# octanis_v0_5.net
KiCad netlist of a schematic drawn in EAGLE
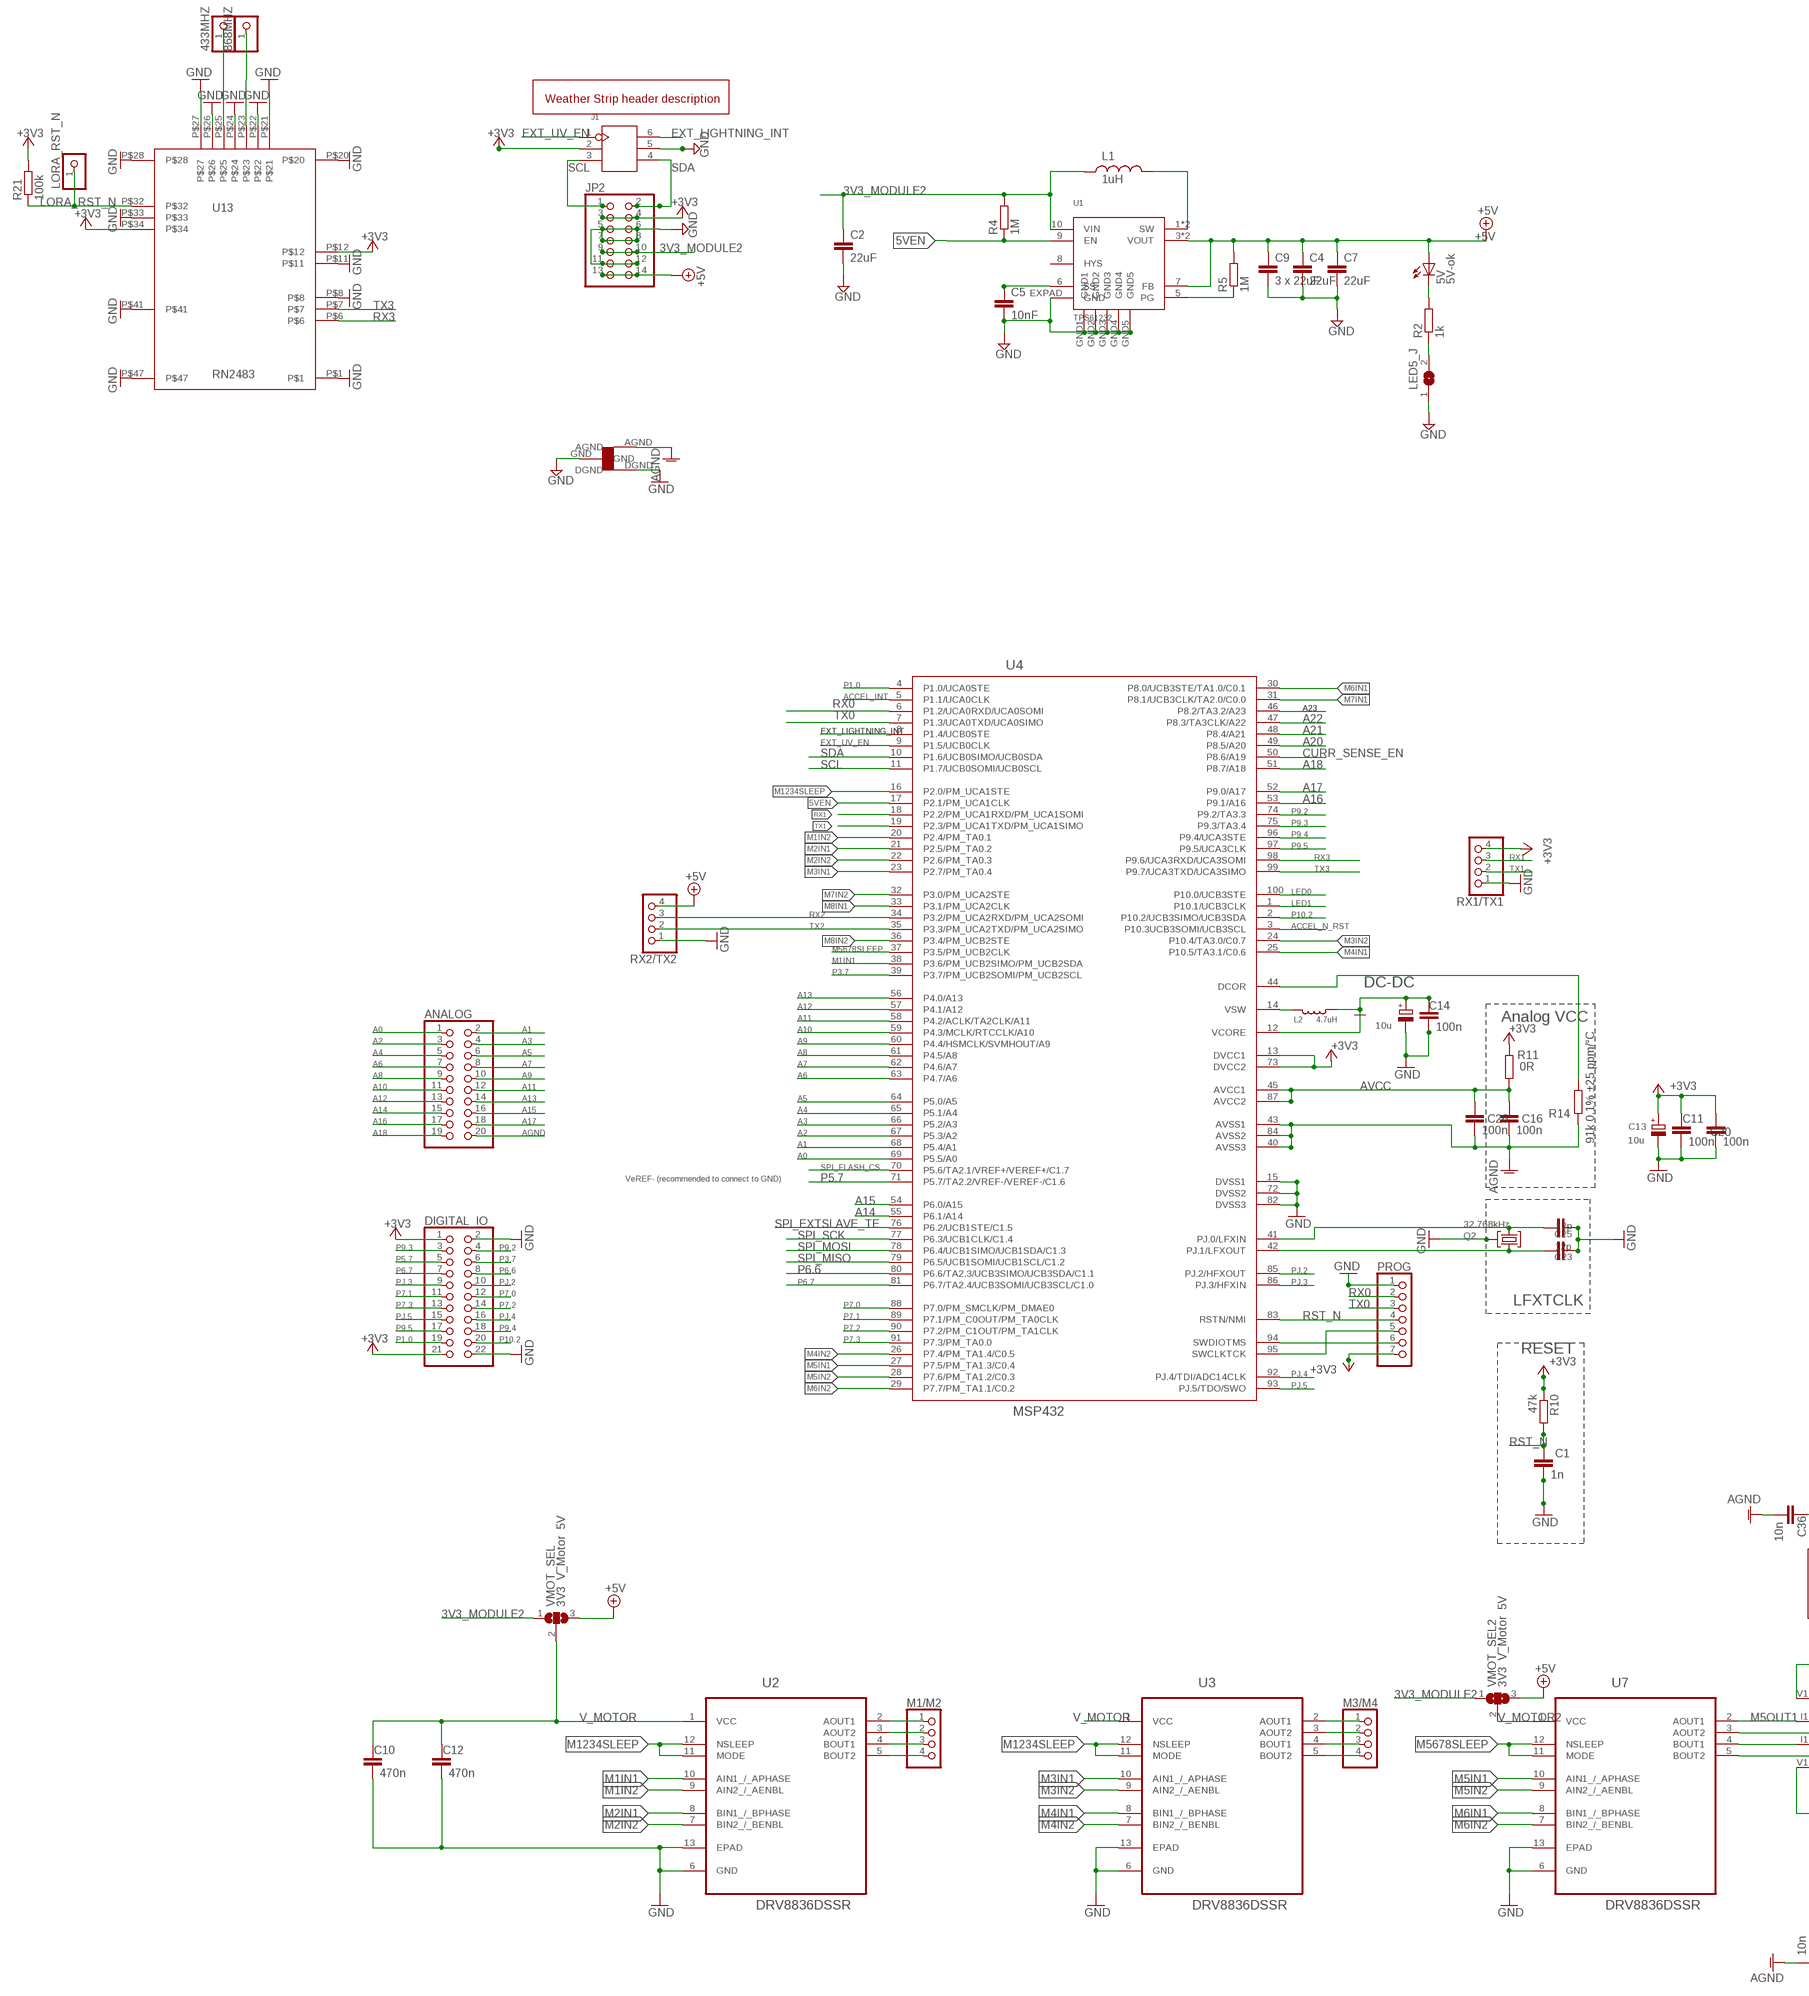
[diagram p0: schematic, sheet 1, part 1 of 2]
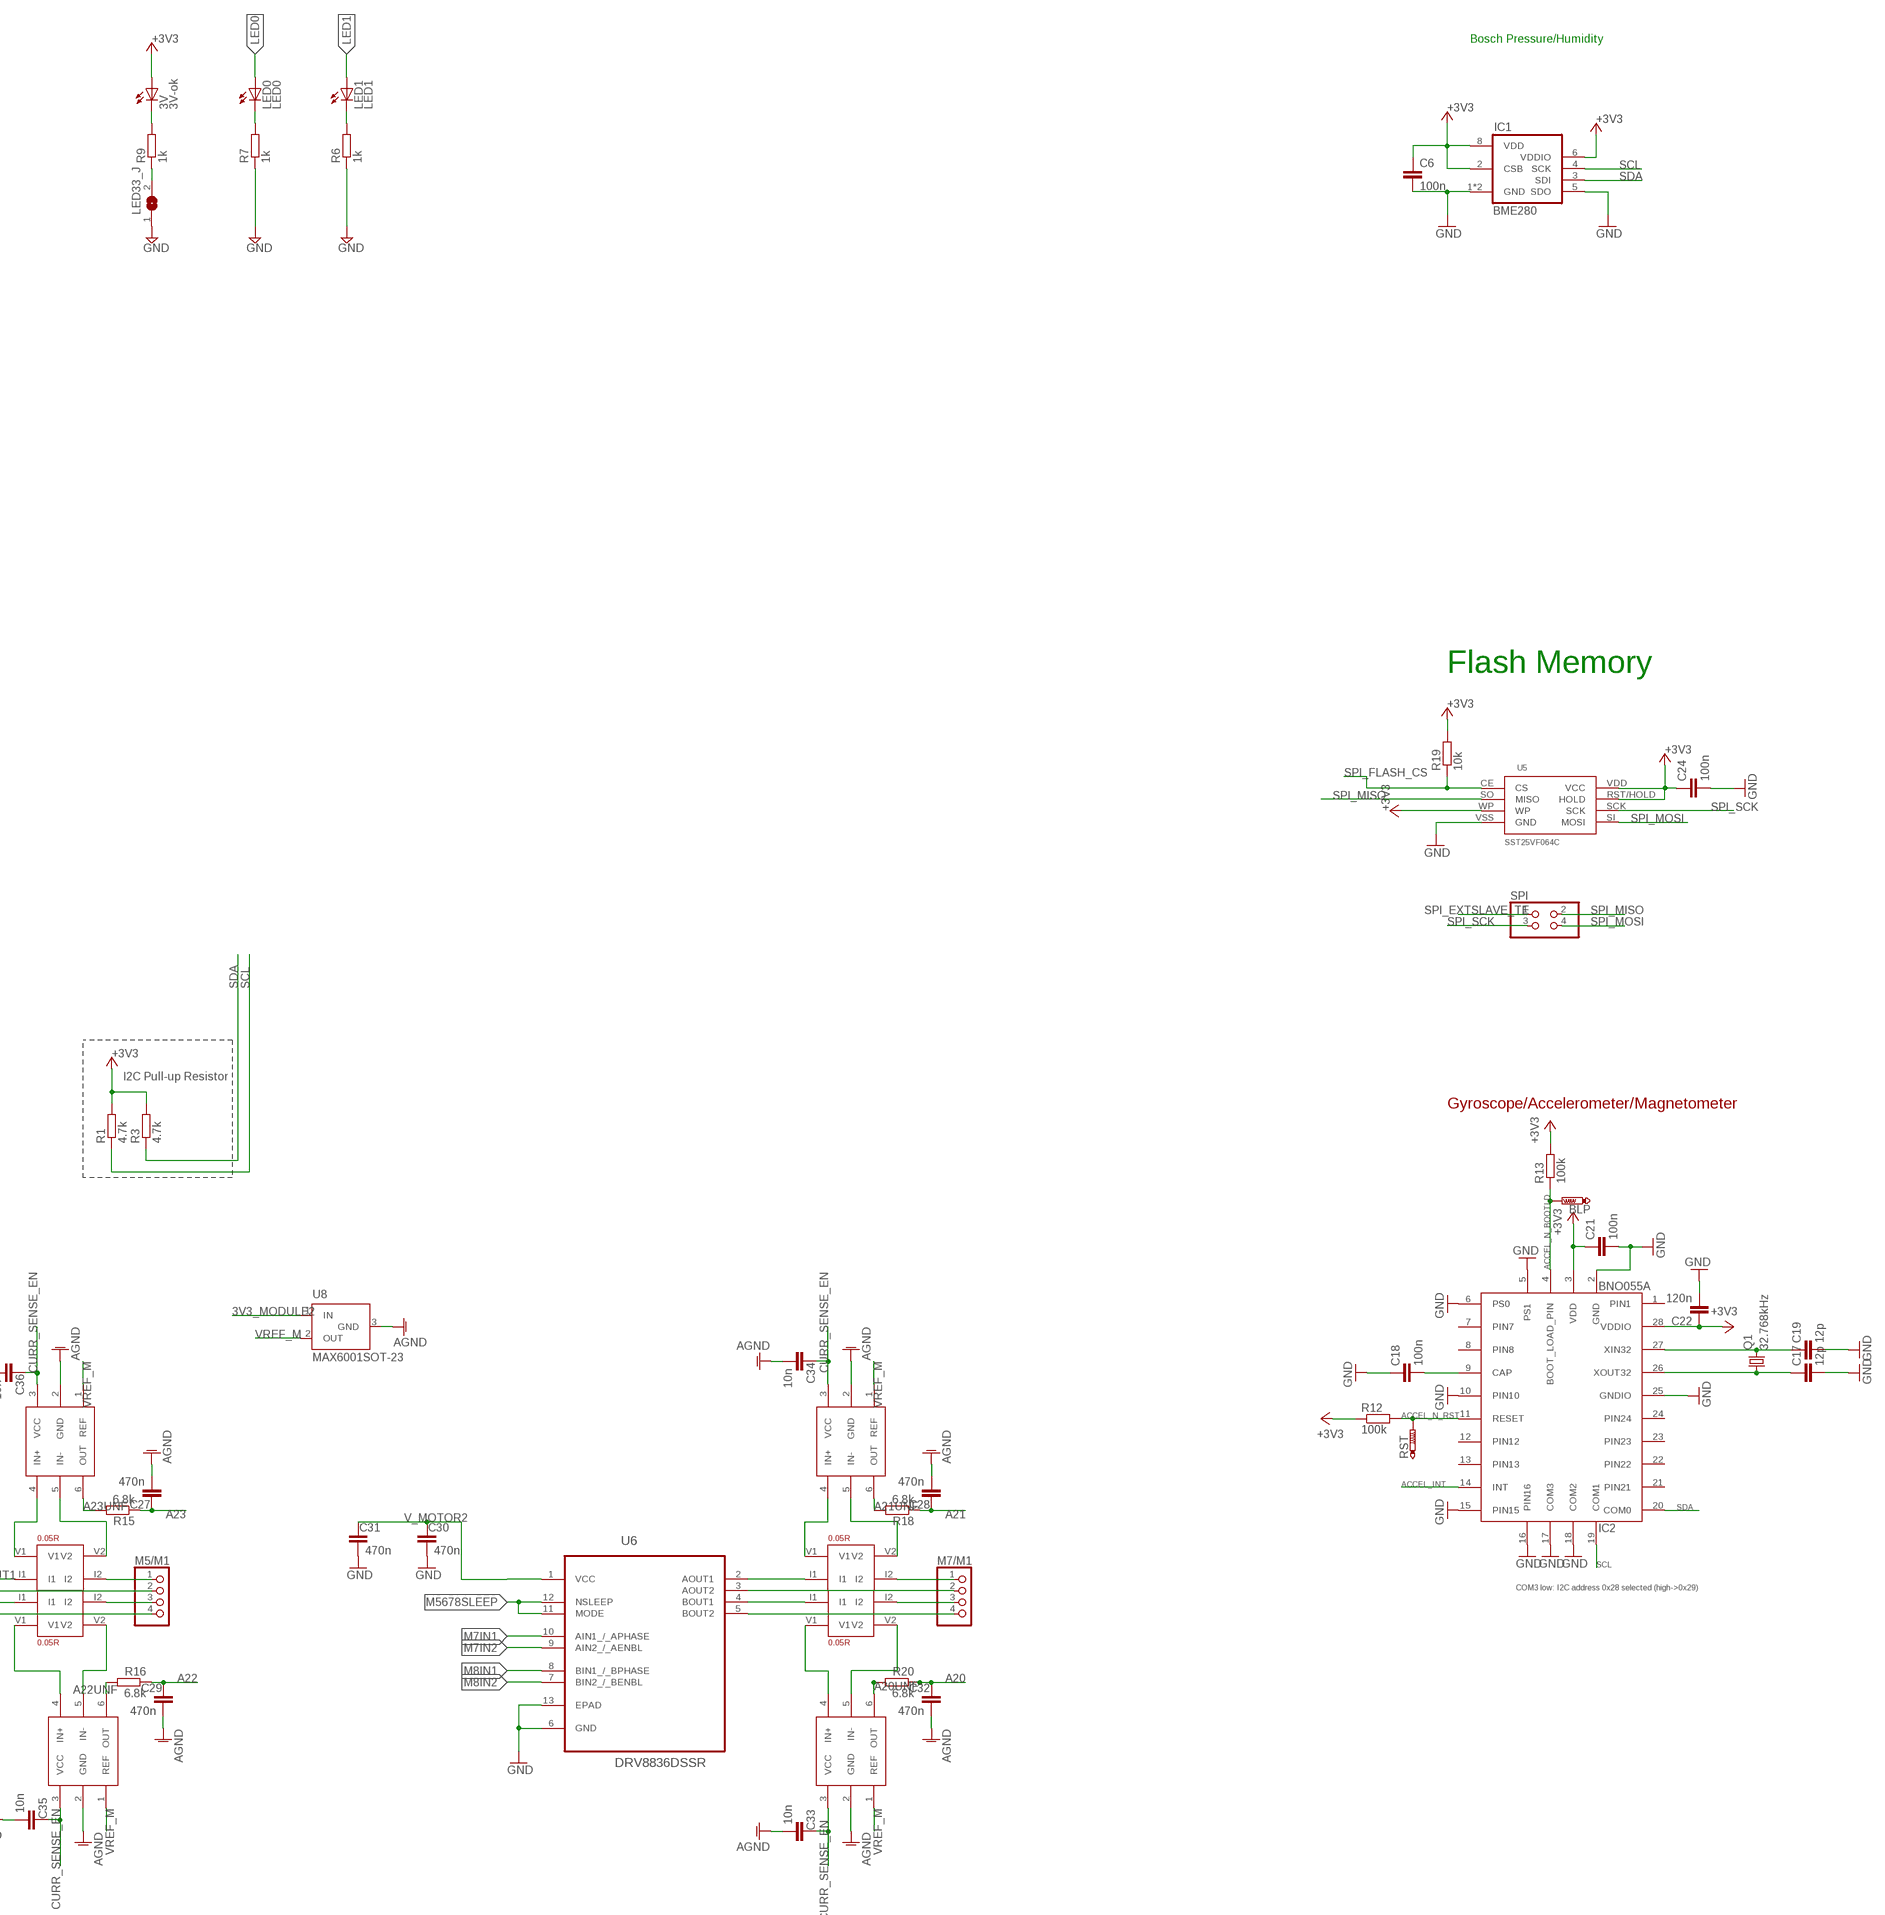
[diagram p1: schematic, sheet 1, part 2 of 2]

(export (version "E")
  (design (tool "Eeschema 10.0.6"))
  (components
    (comp (ref "3V")
      (value "3V-ok")
      (footprint "eagle-import:CHIPLED_0603")
      (libsource (lib "eagle-import") (part "LEDCHIPLED_0603"))
    )
    (comp (ref "5V")
      (value "5V-ok")
      (footprint "eagle-import:CHIPLED_0603")
      (libsource (lib "eagle-import") (part "LEDCHIPLED_0603"))
    )
    (comp (ref "433MHZ")
      (value "PINHD-1X1")
      (footprint "eagle-import:1X01")
      (libsource (lib "eagle-import") (part "PINHD-1X1"))
    )
    (comp (ref "868MHZ")
      (value "PINHD-1X1")
      (footprint "eagle-import:1X01")
      (libsource (lib "eagle-import") (part "PINHD-1X1"))
    )
    (comp (ref "ANALOG")
      (value "PINHD-2X10")
      (footprint "eagle-import:2X10")
      (libsource (lib "eagle-import") (part "PINHD-2X10"))
    )
    (comp (ref "BLP")
      (value "PTR1B1,27")
      (footprint "eagle-import:B1,27")
      (libsource (lib "eagle-import") (part "PTR1B1,27"))
    )
    (comp (ref "C1")
      (value "1n")
      (footprint "eagle-import:C0603")
      (libsource (lib "eagle-import") (part "C-EUC0603"))
    )
    (comp (ref "C2")
      (value "22uF")
      (footprint "eagle-import:C0603")
      (libsource (lib "eagle-import") (part "C-EUC0603"))
    )
    (comp (ref "C4")
      (value "22uF")
      (footprint "eagle-import:C0603")
      (libsource (lib "eagle-import") (part "C-EUC0603"))
    )
    (comp (ref "C5")
      (value "10nF")
      (footprint "eagle-import:C0603")
      (libsource (lib "eagle-import") (part "C-EUC0603"))
    )
    (comp (ref "C6")
      (value "100n")
      (footprint "eagle-import:C0603")
      (libsource (lib "eagle-import") (part "C-EUC0603"))
    )
    (comp (ref "C7")
      (value "22uF")
      (footprint "eagle-import:C0603")
      (libsource (lib "eagle-import") (part "C-EUC0603"))
    )
    (comp (ref "C9")
      (value "3 x 22uF")
      (footprint "eagle-import:C0603")
      (libsource (lib "eagle-import") (part "C-EUC0603"))
    )
    (comp (ref "C10")
      (value "470n")
      (footprint "eagle-import:C0603")
      (libsource (lib "eagle-import") (part "C-EUC0603"))
    )
    (comp (ref "C11")
      (value "100n")
      (footprint "eagle-import:C0603")
      (libsource (lib "eagle-import") (part "C-EUC0603"))
    )
    (comp (ref "C12")
      (value "470n")
      (footprint "eagle-import:C0603")
      (libsource (lib "eagle-import") (part "C-EUC0603"))
    )
    (comp (ref "C13")
      (value "10u")
      (footprint "eagle-import:A_3216-18R")
      (libsource (lib "eagle-import") (part "CPOL-EUA/3216-18R"))
    )
    (comp (ref "C14")
      (value "100n")
      (footprint "eagle-import:C0603")
      (libsource (lib "eagle-import") (part "C-EUC0603"))
    )
    (comp (ref "C15")
      (value "10u")
      (footprint "eagle-import:A_3216-18R")
      (libsource (lib "eagle-import") (part "CPOL-EUA/3216-18R"))
    )
    (comp (ref "C16")
      (value "100n")
      (footprint "eagle-import:C0402")
      (libsource (lib "eagle-import") (part "C-EUC0402"))
    )
    (comp (ref "C17")
      (value "12p")
      (footprint "eagle-import:C0603")
      (libsource (lib "eagle-import") (part "C-EUC0603"))
    )
    (comp (ref "C18")
      (value "100n")
      (footprint "eagle-import:C0603")
      (libsource (lib "eagle-import") (part "C-EUC0603"))
    )
    (comp (ref "C19")
      (value "12p")
      (footprint "eagle-import:C0603")
      (libsource (lib "eagle-import") (part "C-EUC0603"))
    )
    (comp (ref "C20")
      (value "100n")
      (footprint "eagle-import:C0603")
      (libsource (lib "eagle-import") (part "C-EUC0603"))
    )
    (comp (ref "C21")
      (value "100n")
      (footprint "eagle-import:C0603")
      (libsource (lib "eagle-import") (part "C-EUC0603"))
    )
    (comp (ref "C22")
      (value "120n")
      (footprint "eagle-import:C0603")
      (libsource (lib "eagle-import") (part "C-EUC0603"))
    )
    (comp (ref "C23")
      (value "12p")
      (footprint "eagle-import:C0402")
      (libsource (lib "eagle-import") (part "C-EUC0402"))
    )
    (comp (ref "C24")
      (value "100n")
      (footprint "eagle-import:C0603")
      (libsource (lib "eagle-import") (part "C-EUC0603"))
    )
    (comp (ref "C25")
      (value "12p")
      (footprint "eagle-import:C0402")
      (libsource (lib "eagle-import") (part "C-EUC0402"))
    )
    (comp (ref "C26")
      (value "100n")
      (footprint "eagle-import:C0402")
      (libsource (lib "eagle-import") (part "C-EUC0402"))
    )
    (comp (ref "C27")
      (value "470n")
      (footprint "eagle-import:C0603")
      (libsource (lib "eagle-import") (part "C-EUC0603"))
    )
    (comp (ref "C28")
      (value "470n")
      (footprint "eagle-import:C0603")
      (libsource (lib "eagle-import") (part "C-EUC0603"))
    )
    (comp (ref "C29")
      (value "470n")
      (footprint "eagle-import:C0603")
      (libsource (lib "eagle-import") (part "C-EUC0603"))
    )
    (comp (ref "C30")
      (value "470n")
      (footprint "eagle-import:C0603")
      (libsource (lib "eagle-import") (part "C-EUC0603"))
    )
    (comp (ref "C31")
      (value "470n")
      (footprint "eagle-import:C0603")
      (libsource (lib "eagle-import") (part "C-EUC0603"))
    )
    (comp (ref "C32")
      (value "470n")
      (footprint "eagle-import:C0603")
      (libsource (lib "eagle-import") (part "C-EUC0603"))
    )
    (comp (ref "C33")
      (value "10n")
      (footprint "eagle-import:C0603")
      (libsource (lib "eagle-import") (part "C-EUC0603"))
    )
    (comp (ref "C34")
      (value "10n")
      (footprint "eagle-import:C0603")
      (libsource (lib "eagle-import") (part "C-EUC0603"))
    )
    (comp (ref "C35")
      (value "10n")
      (footprint "eagle-import:C0603")
      (libsource (lib "eagle-import") (part "C-EUC0603"))
    )
    (comp (ref "C36")
      (value "10n")
      (footprint "eagle-import:C0603")
      (libsource (lib "eagle-import") (part "C-EUC0603"))
    )
    (comp (ref "DIGITAL_IO")
      (value "PINHD-2X11")
      (footprint "eagle-import:2X11")
      (libsource (lib "eagle-import") (part "PINHD-2X11"))
    )
    (comp (ref "IC1")
      (value "BME280")
      (footprint "eagle-import:BME280")
      (libsource (lib "eagle-import") (part "BME280"))
    )
    (comp (ref "IC2")
      (value "BNO055A")
      (footprint "eagle-import:BNO055")
      (libsource (lib "eagle-import") (part "BNO055A"))
    )
    (comp (ref "J1")
      (value "SMD-BLUE-FEMALE-HEADER-VERT(2X3P-2.54)")
      (footprint "eagle-import:H2X3-SMD-2.54")
      (fields (field (name "MPN") "F185-1203A1BMYA1"))
      (libsource (lib "eagle-import") (part "SMD-BLUE-FEMALE-HEADER-VERT(2X3P-2.54)"))
    )
    (comp (ref "JP2")
      (value "PINHD-2X7")
      (footprint "eagle-import:2X07")
      (libsource (lib "eagle-import") (part "PINHD-2X7"))
    )
    (comp (ref "L1")
      (value "1uH")
      (footprint "eagle-import:XFL4020")
      (libsource (lib "eagle-import") (part "XFL4020"))
    )
    (comp (ref "L2")
      (value "4.7uH")
      (footprint "eagle-import:0806")
      (libsource (lib "eagle-import") (part "LQM2MP_G0"))
    )
    (comp (ref "LED0")
      (value "LED0")
      (footprint "eagle-import:CHIPLED_0603")
      (libsource (lib "eagle-import") (part "LEDCHIPLED_0603"))
    )
    (comp (ref "LED1")
      (value "LED1")
      (footprint "eagle-import:CHIPLED_0603")
      (libsource (lib "eagle-import") (part "LEDCHIPLED_0603"))
    )
    (comp (ref "LED5_J")
      (value "SJ")
      (footprint "eagle-import:SJ")
      (libsource (lib "eagle-import") (part "SJ"))
    )
    (comp (ref "LED33_J")
      (value "SJ")
      (footprint "eagle-import:SJ")
      (libsource (lib "eagle-import") (part "SJ"))
    )
    (comp (ref "LORA_RST_N")
      (value "PINHD-1X1")
      (footprint "eagle-import:1X01")
      (libsource (lib "eagle-import") (part "PINHD-1X1"))
    )
    (comp (ref "M1/M2")
      (value "PINHD-1X04_2.54-S")
      (footprint "eagle-import:1X04-S")
      (libsource (lib "eagle-import") (part "PINHD-1X04_2.54-S"))
    )
    (comp (ref "M3/M4")
      (value "PINHD-1X04_2.54-S")
      (footprint "eagle-import:1X04-S")
      (libsource (lib "eagle-import") (part "PINHD-1X04_2.54-S"))
    )
    (comp (ref "M5/M1")
      (value "PINHD-1X04_2.54-S")
      (footprint "eagle-import:1X04-S")
      (libsource (lib "eagle-import") (part "PINHD-1X04_2.54-S"))
    )
    (comp (ref "M7/M1")
      (value "PINHD-1X04_2.54-S")
      (footprint "eagle-import:1X04-S")
      (libsource (lib "eagle-import") (part "PINHD-1X04_2.54-S"))
    )
    (comp (ref "PROG")
      (value "PINHD-1X72MM_SMD")
      (footprint "eagle-import:1X7SMD")
      (libsource (lib "eagle-import") (part "PINHD-1X72MM_SMD"))
    )
    (comp (ref "Q1")
      (value "32.768kHz")
      (footprint "eagle-import:FC-12M")
      (libsource (lib "eagle-import") (part "FC-12M"))
    )
    (comp (ref "Q2")
      (value "32.768kHz")
      (footprint "eagle-import:MS3V-T1R")
      (libsource (lib "eagle-import") (part "MS3V-T1R"))
    )
    (comp (ref "R1")
      (value "4.7k")
      (footprint "eagle-import:R0603")
      (libsource (lib "eagle-import") (part "R-EU_R0603"))
    )
    (comp (ref "R2")
      (value "1k")
      (footprint "eagle-import:R0603")
      (libsource (lib "eagle-import") (part "R-EU_R0603"))
    )
    (comp (ref "R3")
      (value "4.7k")
      (footprint "eagle-import:R0603")
      (libsource (lib "eagle-import") (part "R-EU_R0603"))
    )
    (comp (ref "R4")
      (value "1M")
      (footprint "eagle-import:R0603")
      (libsource (lib "eagle-import") (part "R-EU_R0603"))
    )
    (comp (ref "R5")
      (value "1M")
      (footprint "eagle-import:R0603")
      (libsource (lib "eagle-import") (part "R-EU_R0603"))
    )
    (comp (ref "R6")
      (value "1k")
      (footprint "eagle-import:R0603")
      (libsource (lib "eagle-import") (part "R-EU_R0603"))
    )
    (comp (ref "R7")
      (value "1k")
      (footprint "eagle-import:R0603")
      (libsource (lib "eagle-import") (part "R-EU_R0603"))
    )
    (comp (ref "R9")
      (value "1k")
      (footprint "eagle-import:R0603")
      (libsource (lib "eagle-import") (part "R-EU_R0603"))
    )
    (comp (ref "R10")
      (value "47k")
      (footprint "eagle-import:R0603")
      (libsource (lib "eagle-import") (part "R-EU_R0603"))
    )
    (comp (ref "R11")
      (value "0R")
      (footprint "eagle-import:R0402")
      (libsource (lib "eagle-import") (part "R-EU_R0402"))
    )
    (comp (ref "R12")
      (value "100k")
      (footprint "eagle-import:R0603")
      (libsource (lib "eagle-import") (part "R-EU_R0603"))
    )
    (comp (ref "R13")
      (value "100k")
      (footprint "eagle-import:R0603")
      (libsource (lib "eagle-import") (part "R-EU_R0603"))
    )
    (comp (ref "R14")
      (value "91k 0.1% ±25 ppm/°C")
      (footprint "eagle-import:R0402")
      (libsource (lib "eagle-import") (part "R-EU_R0402"))
    )
    (comp (ref "R15")
      (value "6.8k")
      (footprint "eagle-import:R0603")
      (libsource (lib "eagle-import") (part "R-EU_R0603"))
    )
    (comp (ref "R16")
      (value "6.8k")
      (footprint "eagle-import:R0603")
      (libsource (lib "eagle-import") (part "R-EU_R0603"))
    )
    (comp (ref "R18")
      (value "6.8k")
      (footprint "eagle-import:R0603")
      (libsource (lib "eagle-import") (part "R-EU_R0603"))
    )
    (comp (ref "R19")
      (value "10k")
      (footprint "eagle-import:R0603")
      (libsource (lib "eagle-import") (part "R-EU_R0603"))
    )
    (comp (ref "R20")
      (value "6.8k")
      (footprint "eagle-import:R0603")
      (libsource (lib "eagle-import") (part "R-EU_R0603"))
    )
    (comp (ref "R21")
      (value "100k")
      (footprint "eagle-import:R0603")
      (libsource (lib "eagle-import") (part "R-EU_R0603"))
    )
    (comp (ref "RS1")
      (value "0.05R")
      (footprint "eagle-import:4PADS_RESISTOR")
      (libsource (lib "eagle-import") (part "CURRENT_RESISTOR"))
    )
    (comp (ref "RS2")
      (value "0.05R")
      (footprint "eagle-import:4PADS_RESISTOR")
      (libsource (lib "eagle-import") (part "CURRENT_RESISTOR"))
    )
    (comp (ref "RS3")
      (value "0.05R")
      (footprint "eagle-import:4PADS_RESISTOR")
      (libsource (lib "eagle-import") (part "CURRENT_RESISTOR"))
    )
    (comp (ref "RS4")
      (value "0.05R")
      (footprint "eagle-import:4PADS_RESISTOR")
      (libsource (lib "eagle-import") (part "CURRENT_RESISTOR"))
    )
    (comp (ref "RST")
      (value "PTR1B1,27")
      (footprint "eagle-import:B1,27")
      (libsource (lib "eagle-import") (part "PTR1B1,27"))
    )
    (comp (ref "RX1/TX1")
      (value "PINHD-1X04_2.54-S")
      (footprint "eagle-import:1X04-S")
      (libsource (lib "eagle-import") (part "PINHD-1X04_2.54-S"))
    )
    (comp (ref "RX2/TX2")
      (value "PINHD-1X04_2.54-S")
      (footprint "eagle-import:1X04-S")
      (libsource (lib "eagle-import") (part "PINHD-1X04_2.54-S"))
    )
    (comp (ref "SPI")
      (value "PINHD-2X2")
      (footprint "eagle-import:2X02")
      (libsource (lib "eagle-import") (part "PINHD-2X2"))
    )
    (comp (ref "U$1")
      (value "WEATHER_STRIP_DOCU")
      (footprint "eagle-import:WEATHER_STRIP_DOCU")
      (libsource (lib "eagle-import") (part "WEATHER_STRIP_DOCU"))
    )
    (comp (ref "U$100")
      (value "STARGND")
      (footprint "eagle-import:STAR")
      (libsource (lib "eagle-import") (part "STARGND"))
    )
    (comp (ref "U1")
      (value "TPS61232")
      (footprint "eagle-import:S-PVSON-N10")
      (libsource (lib "eagle-import") (part "TPS61232"))
    )
    (comp (ref "U2")
      (value "DRV8836DSSR")
      (footprint "eagle-import:SON50P200X300X80-13N")
      (fields (field (name "MPN") "DRV8836DSSR "))
      (libsource (lib "eagle-import") (part "DRV8836DSSR"))
    )
    (comp (ref "U3")
      (value "DRV8836DSSR")
      (footprint "eagle-import:SON50P200X300X80-13N")
      (fields (field (name "MPN") "DRV8836DSSR "))
      (libsource (lib "eagle-import") (part "DRV8836DSSR"))
    )
    (comp (ref "U4")
      (value "MSP432")
      (footprint "eagle-import:PZ100")
      (libsource (lib "eagle-import") (part "MSP432"))
    )
    (comp (ref "U5")
      (value "SST25VF064C")
      (footprint "eagle-import:SOIC_8-LEAD")
      (libsource (lib "eagle-import") (part "SST25VF064C"))
    )
    (comp (ref "U6")
      (value "DRV8836DSSR")
      (footprint "eagle-import:SON50P200X300X80-13N")
      (fields (field (name "MPN") "DRV8836DSSR "))
      (libsource (lib "eagle-import") (part "DRV8836DSSR"))
    )
    (comp (ref "U7")
      (value "DRV8836DSSR")
      (footprint "eagle-import:SON50P200X300X80-13N")
      (fields (field (name "MPN") "DRV8836DSSR "))
      (libsource (lib "eagle-import") (part "DRV8836DSSR"))
    )
    (comp (ref "U8")
      (value "MAX6001SOT-23")
      (footprint "eagle-import:MAX6001")
      (libsource (lib "eagle-import") (part "MAX6001SOT-23"))
    )
    (comp (ref "U9")
      (value "INA210")
      (footprint "eagle-import:SC70-6")
      (libsource (lib "eagle-import") (part "INA213"))
    )
    (comp (ref "U10")
      (value "INA210")
      (footprint "eagle-import:SC70-6")
      (libsource (lib "eagle-import") (part "INA213"))
    )
    (comp (ref "U11")
      (value "INA210")
      (footprint "eagle-import:SC70-6")
      (libsource (lib "eagle-import") (part "INA213"))
    )
    (comp (ref "U12")
      (value "INA210")
      (footprint "eagle-import:SC70-6")
      (libsource (lib "eagle-import") (part "INA213"))
    )
    (comp (ref "U13")
      (value "RN2483")
      (footprint "eagle-import:RN2483")
      (libsource (lib "eagle-import") (part "RN2483"))
    )
    (comp (ref "VMOT_SEL")
      (value "3V3 V_Motor 5V")
      (footprint "eagle-import:SJ_2")
      (libsource (lib "eagle-import") (part "SJ2W"))
    )
    (comp (ref "VMOT_SEL2")
      (value "3V3 V_Motor 5V")
      (footprint "eagle-import:SJ_2")
      (libsource (lib "eagle-import") (part "SJ2W"))
    )
  )
  (nets
    (net (code "1") (name "+3V3") (class "Default")
      (node (ref "3V") (pin "A") (pinfunction "A_A") (pintype "passive"))
      (node (ref "C11") (pin "2") (pinfunction "2_2") (pintype "passive"))
      (node (ref "C13") (pin "+") (pinfunction "+_+") (pintype "passive"))
      (node (ref "C20") (pin "2") (pinfunction "2_2") (pintype "passive"))
      (node (ref "C21") (pin "1") (pinfunction "1_1") (pintype "passive"))
      (node (ref "C22") (pin "1") (pinfunction "1_1") (pintype "passive"))
      (node (ref "C24") (pin "1") (pinfunction "1_1") (pintype "passive"))
      (node (ref "C6") (pin "1") (pinfunction "1_1") (pintype "passive"))
      (node (ref "DIGITAL_IO") (pin "1") (pinfunction "1_1") (pintype "passive"))
      (node (ref "DIGITAL_IO") (pin "21") (pinfunction "21_21") (pintype "passive"))
      (node (ref "IC1") (pin "2") (pinfunction "CSB_2") (pintype "input"))
      (node (ref "IC1") (pin "6") (pinfunction "VDDIO_6") (pintype "power_in"))
      (node (ref "IC1") (pin "8") (pinfunction "VDD_8") (pintype "power_in"))
      (node (ref "IC2") (pin "28") (pinfunction "VDDIO_28") (pintype "bidirectional"))
      (node (ref "IC2") (pin "3") (pinfunction "VDD_3") (pintype "bidirectional"))
      (node (ref "J1") (pin "2") (pinfunction "2_2") (pintype "bidirectional"))
      (node (ref "JP2") (pin "3") (pinfunction "3_3") (pintype "passive"))
      (node (ref "JP2") (pin "4") (pinfunction "4_4") (pintype "passive"))
      (node (ref "PROG") (pin "7") (pinfunction "7_7") (pintype "passive"))
      (node (ref "R1") (pin "2") (pinfunction "2_2") (pintype "passive"))
      (node (ref "R10") (pin "1") (pinfunction "1_1") (pintype "passive"))
      (node (ref "R11") (pin "2") (pinfunction "2_2") (pintype "passive"))
      (node (ref "R12") (pin "1") (pinfunction "1_1") (pintype "passive"))
      (node (ref "R13") (pin "2") (pinfunction "2_2") (pintype "passive"))
      (node (ref "R19") (pin "2") (pinfunction "2_2") (pintype "passive"))
      (node (ref "R21") (pin "2") (pinfunction "2_2") (pintype "passive"))
      (node (ref "R3") (pin "2") (pinfunction "2_2") (pintype "passive"))
      (node (ref "RX1/TX1") (pin "4") (pinfunction "4_4") (pintype "passive"))
      (node (ref "U13") (pin "P$12") (pinfunction "P$12_P$12") (pintype "bidirectional"))
      (node (ref "U13") (pin "P$34") (pinfunction "P$34_P$34") (pintype "bidirectional"))
      (node (ref "U4") (pin "13") (pinfunction "DVCC1_13") (pintype "power_in"))
      (node (ref "U4") (pin "73") (pinfunction "DVCC2_73") (pintype "power_in"))
      (node (ref "U5") (pin "RST/HOLD") (pinfunction "HOLD_RST/HOLD") (pintype "bidirectional"))
      (node (ref "U5") (pin "VDD") (pinfunction "VCC_VDD") (pintype "bidirectional"))
      (node (ref "U5") (pin "WP") (pinfunction "WP_WP") (pintype "bidirectional"))
    )
    (net (code "2") (name "+5V") (class "Default")
      (node (ref "5V") (pin "A") (pinfunction "A_A") (pintype "passive"))
      (node (ref "C4") (pin "1") (pinfunction "1_1") (pintype "passive"))
      (node (ref "C7") (pin "1") (pinfunction "1_1") (pintype "passive"))
      (node (ref "C9") (pin "1") (pinfunction "1_1") (pintype "passive"))
      (node (ref "JP2") (pin "13") (pinfunction "13_13") (pintype "passive"))
      (node (ref "JP2") (pin "14") (pinfunction "14_14") (pintype "passive"))
      (node (ref "R5") (pin "2") (pinfunction "2_2") (pintype "passive"))
      (node (ref "RX2/TX2") (pin "4") (pinfunction "4_4") (pintype "passive"))
      (node (ref "U1") (pin "3") (pinfunction "VOUT_3") (pintype "power_in"))
      (node (ref "U1") (pin "4") (pinfunction "VOUT_4") (pintype "power_in"))
      (node (ref "U1") (pin "7") (pinfunction "FB_7") (pintype "input"))
      (node (ref "VMOT_SEL") (pin "3") (pinfunction "3_3") (pintype "passive"))
      (node (ref "VMOT_SEL2") (pin "3") (pinfunction "3_3") (pintype "passive"))
    )
    (net (code "3") (name "/3V3_MODULE2") (class "Default")
      (node (ref "C2") (pin "1") (pinfunction "1_1") (pintype "passive"))
      (node (ref "JP2") (pin "10") (pinfunction "10_10") (pintype "passive"))
      (node (ref "JP2") (pin "9") (pinfunction "9_9") (pintype "passive"))
      (node (ref "L1") (pin "P$1") (pinfunction "1_P$1") (pintype "passive"))
      (node (ref "R4") (pin "2") (pinfunction "2_2") (pintype "passive"))
      (node (ref "U1") (pin "10") (pinfunction "VIN_10") (pintype "input"))
      (node (ref "U8") (pin "1") (pinfunction "IN_1") (pintype "input"))
      (node (ref "VMOT_SEL") (pin "1") (pinfunction "1_1") (pintype "passive"))
      (node (ref "VMOT_SEL2") (pin "1") (pinfunction "1_1") (pintype "passive"))
    )
    (net (code "4") (name "/A0") (class "Default")
      (node (ref "ANALOG") (pin "1") (pinfunction "1_1") (pintype "passive"))
      (node (ref "U4") (pin "69") (pinfunction "P5.5/A0_69") (pintype "power_in"))
    )
    (net (code "5") (name "/A1") (class "Default")
      (node (ref "ANALOG") (pin "2") (pinfunction "2_2") (pintype "passive"))
      (node (ref "U4") (pin "68") (pinfunction "P5.4/A1_68") (pintype "power_in"))
    )
    (net (code "6") (name "/A2") (class "Default")
      (node (ref "ANALOG") (pin "3") (pinfunction "3_3") (pintype "passive"))
      (node (ref "U4") (pin "67") (pinfunction "P5.3/A2_67") (pintype "power_in"))
    )
    (net (code "7") (name "/A3") (class "Default")
      (node (ref "ANALOG") (pin "4") (pinfunction "4_4") (pintype "passive"))
      (node (ref "U4") (pin "66") (pinfunction "P5.2/A3_66") (pintype "power_in"))
    )
    (net (code "8") (name "/A4") (class "Default")
      (node (ref "ANALOG") (pin "5") (pinfunction "5_5") (pintype "passive"))
      (node (ref "U4") (pin "65") (pinfunction "P5.1/A4_65") (pintype "power_in"))
    )
    (net (code "9") (name "/A5") (class "Default")
      (node (ref "ANALOG") (pin "6") (pinfunction "6_6") (pintype "passive"))
      (node (ref "U4") (pin "64") (pinfunction "P5.0/A5_64") (pintype "power_in"))
    )
    (net (code "10") (name "/A6") (class "Default")
      (node (ref "ANALOG") (pin "7") (pinfunction "7_7") (pintype "passive"))
      (node (ref "U4") (pin "63") (pinfunction "P4.7/A6_63") (pintype "power_in"))
    )
    (net (code "11") (name "/A7") (class "Default")
      (node (ref "ANALOG") (pin "8") (pinfunction "8_8") (pintype "passive"))
      (node (ref "U4") (pin "62") (pinfunction "P4.6/A7_62") (pintype "power_in"))
    )
    (net (code "12") (name "/A8") (class "Default")
      (node (ref "ANALOG") (pin "9") (pinfunction "9_9") (pintype "passive"))
      (node (ref "U4") (pin "61") (pinfunction "P4.5/A8_61") (pintype "power_in"))
    )
    (net (code "13") (name "/A9") (class "Default")
      (node (ref "ANALOG") (pin "10") (pinfunction "10_10") (pintype "passive"))
      (node (ref "U4") (pin "60") (pinfunction "P4.4/HSMCLK/SVMHOUT/A9_60") (pintype "power_in"))
    )
    (net (code "14") (name "/A10") (class "Default")
      (node (ref "ANALOG") (pin "11") (pinfunction "11_11") (pintype "passive"))
      (node (ref "U4") (pin "59") (pinfunction "P4.3/MCLK/RTCCLK/A10_59") (pintype "power_in"))
    )
    (net (code "15") (name "/A11") (class "Default")
      (node (ref "ANALOG") (pin "12") (pinfunction "12_12") (pintype "passive"))
      (node (ref "U4") (pin "58") (pinfunction "P4.2/ACLK/TA2CLK/A11_58") (pintype "power_in"))
    )
    (net (code "16") (name "/A12") (class "Default")
      (node (ref "ANALOG") (pin "13") (pinfunction "13_13") (pintype "passive"))
      (node (ref "U4") (pin "57") (pinfunction "P4.1/A12_57") (pintype "power_in"))
    )
    (net (code "17") (name "/A13") (class "Default")
      (node (ref "ANALOG") (pin "14") (pinfunction "14_14") (pintype "passive"))
      (node (ref "U4") (pin "56") (pinfunction "P4.0/A13_56") (pintype "power_in"))
    )
    (net (code "18") (name "/A14") (class "Default")
      (node (ref "ANALOG") (pin "15") (pinfunction "15_15") (pintype "passive"))
      (node (ref "U4") (pin "55") (pinfunction "P6.1/A14_55") (pintype "power_in"))
    )
    (net (code "19") (name "/A15") (class "Default")
      (node (ref "ANALOG") (pin "16") (pinfunction "16_16") (pintype "passive"))
      (node (ref "U4") (pin "54") (pinfunction "P6.0/A15_54") (pintype "power_in"))
    )
    (net (code "20") (name "/A16") (class "Default")
      (node (ref "ANALOG") (pin "17") (pinfunction "17_17") (pintype "passive"))
      (node (ref "U4") (pin "53") (pinfunction "P9.1/A16_53") (pintype "power_in"))
    )
    (net (code "21") (name "/A17") (class "Default")
      (node (ref "ANALOG") (pin "18") (pinfunction "18_18") (pintype "passive"))
      (node (ref "U4") (pin "52") (pinfunction "P9.0/A17_52") (pintype "power_in"))
    )
    (net (code "22") (name "/A18") (class "Default")
      (node (ref "ANALOG") (pin "19") (pinfunction "19_19") (pintype "passive"))
      (node (ref "U4") (pin "51") (pinfunction "P8.7/A18_51") (pintype "power_in"))
    )
    (net (code "23") (name "/A20") (class "Default")
      (node (ref "C32") (pin "2") (pinfunction "2_2") (pintype "passive"))
      (node (ref "R20") (pin "1") (pinfunction "1_1") (pintype "passive"))
      (node (ref "U4") (pin "49") (pinfunction "P8.5/A20_49") (pintype "power_in"))
    )
    (net (code "24") (name "/A20UNF") (class "Default")
      (node (ref "R20") (pin "2") (pinfunction "2_2") (pintype "passive"))
      (node (ref "U9") (pin "6") (pinfunction "OUT_6") (pintype "bidirectional"))
    )
    (net (code "25") (name "/A21") (class "Default")
      (node (ref "C28") (pin "2") (pinfunction "2_2") (pintype "passive"))
      (node (ref "R18") (pin "1") (pinfunction "1_1") (pintype "passive"))
      (node (ref "U4") (pin "48") (pinfunction "P8.4/A21_48") (pintype "power_in"))
    )
    (net (code "26") (name "/A21UNF") (class "Default")
      (node (ref "R18") (pin "2") (pinfunction "2_2") (pintype "passive"))
      (node (ref "U10") (pin "6") (pinfunction "OUT_6") (pintype "bidirectional"))
    )
    (net (code "27") (name "/A22") (class "Default")
      (node (ref "C29") (pin "2") (pinfunction "2_2") (pintype "passive"))
      (node (ref "R16") (pin "1") (pinfunction "1_1") (pintype "passive"))
      (node (ref "U4") (pin "47") (pinfunction "P8.3/TA3CLK/A22_47") (pintype "power_in"))
    )
    (net (code "28") (name "/A22UNF") (class "Default")
      (node (ref "R16") (pin "2") (pinfunction "2_2") (pintype "passive"))
      (node (ref "U11") (pin "6") (pinfunction "OUT_6") (pintype "bidirectional"))
    )
    (net (code "29") (name "/A23") (class "Default")
      (node (ref "C27") (pin "2") (pinfunction "2_2") (pintype "passive"))
      (node (ref "R15") (pin "1") (pinfunction "1_1") (pintype "passive"))
      (node (ref "U4") (pin "46") (pinfunction "P8.2/TA3.2/A23_46") (pintype "power_in"))
    )
    (net (code "30") (name "/A23UNF") (class "Default")
      (node (ref "R15") (pin "2") (pinfunction "2_2") (pintype "passive"))
      (node (ref "U12") (pin "6") (pinfunction "OUT_6") (pintype "bidirectional"))
    )
    (net (code "31") (name "/ACCEL_INT") (class "Default")
      (node (ref "IC2") (pin "14") (pinfunction "INT_14") (pintype "bidirectional"))
      (node (ref "U4") (pin "5") (pinfunction "P1.1/UCA0CLK_5") (pintype "power_in"))
    )
    (net (code "32") (name "/ACCEL_N_BOOTLD") (class "Default")
      (node (ref "BLP") (pin "TP") (pinfunction "TP_TP") (pintype "input"))
      (node (ref "IC2") (pin "4") (pinfunction "BOOT_LOAD_PIN_4") (pintype "bidirectional"))
      (node (ref "R13") (pin "1") (pinfunction "1_1") (pintype "passive"))
    )
    (net (code "33") (name "/ACCEL_N_RST") (class "Default")
      (node (ref "IC2") (pin "11") (pinfunction "RESET_11") (pintype "bidirectional"))
      (node (ref "R12") (pin "2") (pinfunction "2_2") (pintype "passive"))
      (node (ref "RST") (pin "TP") (pinfunction "TP_TP") (pintype "input"))
      (node (ref "U4") (pin "3") (pinfunction "P10.3UCB3SOMI/UCB3SCL_3") (pintype "power_in"))
    )
    (net (code "34") (name "/AVCC") (class "Default")
      (node (ref "C16") (pin "1") (pinfunction "1_1") (pintype "passive"))
      (node (ref "C26") (pin "1") (pinfunction "1_1") (pintype "passive"))
      (node (ref "R11") (pin "1") (pinfunction "1_1") (pintype "passive"))
      (node (ref "U4") (pin "45") (pinfunction "AVCC1_45") (pintype "power_in"))
      (node (ref "U4") (pin "87") (pinfunction "AVCC2_87") (pintype "power_in"))
    )
    (net (code "35") (name "/CURR_SENSE_EN") (class "Default")
      (node (ref "C33") (pin "2") (pinfunction "2_2") (pintype "passive"))
      (node (ref "C34") (pin "2") (pinfunction "2_2") (pintype "passive"))
      (node (ref "C35") (pin "2") (pinfunction "2_2") (pintype "passive"))
      (node (ref "C36") (pin "2") (pinfunction "2_2") (pintype "passive"))
      (node (ref "U10") (pin "3") (pinfunction "VCC_3") (pintype "bidirectional"))
      (node (ref "U11") (pin "3") (pinfunction "VCC_3") (pintype "bidirectional"))
      (node (ref "U12") (pin "3") (pinfunction "VCC_3") (pintype "bidirectional"))
      (node (ref "U4") (pin "50") (pinfunction "P8.6/A19_50") (pintype "power_in"))
      (node (ref "U9") (pin "3") (pinfunction "VCC_3") (pintype "bidirectional"))
    )
    (net (code "36") (name "/EXT_LIGHTNING_INT") (class "Default")
      (node (ref "J1") (pin "6") (pinfunction "6_6") (pintype "bidirectional"))
      (node (ref "U4") (pin "8") (pinfunction "P1.4/UCB0STE_8") (pintype "power_in"))
    )
    (net (code "37") (name "/EXT_UV_EN") (class "Default")
      (node (ref "J1") (pin "1") (pinfunction "1_1") (pintype "bidirectional"))
      (node (ref "U4") (pin "9") (pinfunction "P1.5/UCB0CLK_9") (pintype "power_in"))
    )
    (net (code "38") (name "/LORA_RST_N") (class "Default")
      (node (ref "LORA_RST_N") (pin "1") (pinfunction "1_1") (pintype "passive"))
      (node (ref "R21") (pin "1") (pinfunction "1_1") (pintype "passive"))
      (node (ref "U13") (pin "P$32") (pinfunction "P$32_P$32") (pintype "bidirectional"))
    )
    (net (code "39") (name "/M5OUT1") (class "Default")
      (node (ref "RS4") (pin "I1") (pinfunction "I1_I1") (pintype "bidirectional"))
      (node (ref "U7") (pin "2") (pinfunction "AOUT1_2") (pintype "output"))
    )
    (net (code "40") (name "/P1.0") (class "Default")
      (node (ref "DIGITAL_IO") (pin "19") (pinfunction "19_19") (pintype "passive"))
      (node (ref "U4") (pin "4") (pinfunction "P1.0/UCA0STE_4") (pintype "power_in"))
    )
    (net (code "41") (name "/P3.7") (class "Default")
      (node (ref "DIGITAL_IO") (pin "6") (pinfunction "6_6") (pintype "passive"))
      (node (ref "U4") (pin "39") (pinfunction "P3.7/PM_UCB2SOMI/PM_UCB2SCL_39") (pintype "power_in"))
    )
    (net (code "42") (name "/P5.7") (class "Default")
      (node (ref "DIGITAL_IO") (pin "5") (pinfunction "5_5") (pintype "passive"))
      (node (ref "U4") (pin "71") (pinfunction "P5.7/TA2.2/VREF-/VEREF-/C1.6_71") (pintype "power_in"))
    )
    (net (code "43") (name "/P6.6") (class "Default")
      (node (ref "DIGITAL_IO") (pin "8") (pinfunction "8_8") (pintype "passive"))
      (node (ref "U4") (pin "80") (pinfunction "P6.6/TA2.3/UCB3SIMO/UCB3SDA/C1.1_80") (pintype "power_in"))
    )
    (net (code "44") (name "/P6.7") (class "Default")
      (node (ref "DIGITAL_IO") (pin "7") (pinfunction "7_7") (pintype "passive"))
      (node (ref "U4") (pin "81") (pinfunction "P6.7/TA2.4/UCB3SOMI/UCB3SCL/C1.0_81") (pintype "power_in"))
    )
    (net (code "45") (name "/P7.0") (class "Default")
      (node (ref "DIGITAL_IO") (pin "12") (pinfunction "12_12") (pintype "passive"))
      (node (ref "U4") (pin "88") (pinfunction "P7.0/PM_SMCLK/PM_DMAE0_88") (pintype "power_in"))
    )
    (net (code "46") (name "/P7.1") (class "Default")
      (node (ref "DIGITAL_IO") (pin "11") (pinfunction "11_11") (pintype "passive"))
      (node (ref "U4") (pin "89") (pinfunction "P7.1/PM_C0OUT/PM_TA0CLK_89") (pintype "power_in"))
    )
    (net (code "47") (name "/P7.2") (class "Default")
      (node (ref "DIGITAL_IO") (pin "14") (pinfunction "14_14") (pintype "passive"))
      (node (ref "U4") (pin "90") (pinfunction "P7.2/PM_C1OUT/PM_TA1CLK_90") (pintype "power_in"))
    )
    (net (code "48") (name "/P7.3") (class "Default")
      (node (ref "DIGITAL_IO") (pin "13") (pinfunction "13_13") (pintype "passive"))
      (node (ref "U4") (pin "91") (pinfunction "P7.3/PM_TA0.0_91") (pintype "power_in"))
    )
    (net (code "49") (name "/P9.2") (class "Default")
      (node (ref "DIGITAL_IO") (pin "4") (pinfunction "4_4") (pintype "passive"))
      (node (ref "U4") (pin "74") (pinfunction "P9.2/TA3.3_74") (pintype "power_in"))
    )
    (net (code "50") (name "/P9.3") (class "Default")
      (node (ref "DIGITAL_IO") (pin "3") (pinfunction "3_3") (pintype "passive"))
      (node (ref "U4") (pin "75") (pinfunction "P9.3/TA3.4_75") (pintype "power_in"))
    )
    (net (code "51") (name "/P9.4") (class "Default")
      (node (ref "DIGITAL_IO") (pin "18") (pinfunction "18_18") (pintype "passive"))
      (node (ref "U4") (pin "96") (pinfunction "P9.4/UCA3STE_96") (pintype "power_in"))
    )
    (net (code "52") (name "/P9.5") (class "Default")
      (node (ref "DIGITAL_IO") (pin "17") (pinfunction "17_17") (pintype "passive"))
      (node (ref "U4") (pin "97") (pinfunction "P9.5/UCA3CLK_97") (pintype "power_in"))
    )
    (net (code "53") (name "/P10.2") (class "Default")
      (node (ref "DIGITAL_IO") (pin "20") (pinfunction "20_20") (pintype "passive"))
      (node (ref "U4") (pin "2") (pinfunction "P10.2/UCB3SIMO/UCB3SDA_2") (pintype "power_in"))
    )
    (net (code "54") (name "/PJ.2") (class "Default")
      (node (ref "DIGITAL_IO") (pin "10") (pinfunction "10_10") (pintype "passive"))
      (node (ref "U4") (pin "85") (pinfunction "PJ.2/HFXOUT_85") (pintype "power_in"))
    )
    (net (code "55") (name "/PJ.3") (class "Default")
      (node (ref "DIGITAL_IO") (pin "9") (pinfunction "9_9") (pintype "passive"))
      (node (ref "U4") (pin "86") (pinfunction "PJ.3/HFXIN_86") (pintype "power_in"))
    )
    (net (code "56") (name "/PJ.4") (class "Default")
      (node (ref "DIGITAL_IO") (pin "16") (pinfunction "16_16") (pintype "passive"))
      (node (ref "U4") (pin "92") (pinfunction "PJ.4/TDI/ADC14CLK_92") (pintype "power_in"))
    )
    (net (code "57") (name "/PJ.5") (class "Default")
      (node (ref "DIGITAL_IO") (pin "15") (pinfunction "15_15") (pintype "passive"))
      (node (ref "U4") (pin "93") (pinfunction "PJ.5/TDO/SWO_93") (pintype "power_in"))
    )
    (net (code "58") (name "/RST_N") (class "Default")
      (node (ref "C1") (pin "2") (pinfunction "2_2") (pintype "passive"))
      (node (ref "PROG") (pin "4") (pinfunction "4_4") (pintype "passive"))
      (node (ref "R10") (pin "2") (pinfunction "2_2") (pintype "passive"))
      (node (ref "U4") (pin "83") (pinfunction "RSTN/NMI_83") (pintype "power_in"))
    )
    (net (code "59") (name "/RX0") (class "Default")
      (node (ref "PROG") (pin "2") (pinfunction "2_2") (pintype "passive"))
      (node (ref "U4") (pin "6") (pinfunction "P1.2/UCA0RXD/UCA0SOMI_6") (pintype "power_in"))
    )
    (net (code "60") (name "/RX2") (class "Default")
      (node (ref "RX2/TX2") (pin "3") (pinfunction "3_3") (pintype "passive"))
      (node (ref "U4") (pin "34") (pinfunction "P3.2/PM_UCA2RXD/PM_UCA2SOMI_34") (pintype "power_in"))
    )
    (net (code "61") (name "/RX3") (class "Default")
      (node (ref "U13") (pin "P$6") (pinfunction "P$6_P$6") (pintype "bidirectional"))
      (node (ref "U4") (pin "98") (pinfunction "P9.6/UCA3RXD/UCA3SOMI_98") (pintype "power_in"))
    )
    (net (code "62") (name "/SCL") (class "Default")
      (node (ref "IC1") (pin "4") (pinfunction "SCK_4") (pintype "bidirectional"))
      (node (ref "IC2") (pin "19") (pinfunction "COM1_19") (pintype "bidirectional"))
      (node (ref "J1") (pin "3") (pinfunction "3_3") (pintype "bidirectional"))
      (node (ref "JP2") (pin "1") (pinfunction "1_1") (pintype "passive"))
      (node (ref "R1") (pin "1") (pinfunction "1_1") (pintype "passive"))
      (node (ref "U4") (pin "11") (pinfunction "P1.7/UCB0SOMI/UCB0SCL_11") (pintype "power_in"))
    )
    (net (code "63") (name "/SDA") (class "Default")
      (node (ref "IC1") (pin "3") (pinfunction "SDI_3") (pintype "bidirectional"))
      (node (ref "IC2") (pin "20") (pinfunction "COM0_20") (pintype "bidirectional"))
      (node (ref "J1") (pin "4") (pinfunction "4_4") (pintype "bidirectional"))
      (node (ref "JP2") (pin "2") (pinfunction "2_2") (pintype "passive"))
      (node (ref "R3") (pin "1") (pinfunction "1_1") (pintype "passive"))
      (node (ref "U4") (pin "10") (pinfunction "P1.6/UCB0SIMO/UCB0SDA_10") (pintype "power_in"))
    )
    (net (code "64") (name "/SPI_EXTSLAVE_TE") (class "Default")
      (node (ref "SPI") (pin "1") (pinfunction "1_1") (pintype "passive"))
      (node (ref "U4") (pin "76") (pinfunction "P6.2/UCB1STE/C1.5_76") (pintype "power_in"))
    )
    (net (code "65") (name "/SPI_FLASH_CS") (class "Default")
      (node (ref "R19") (pin "1") (pinfunction "1_1") (pintype "passive"))
      (node (ref "U4") (pin "70") (pinfunction "P5.6/TA2.1/VREF+/VEREF+/C1.7_70") (pintype "power_in"))
      (node (ref "U5") (pin "CE") (pinfunction "CS_CE") (pintype "bidirectional"))
    )
    (net (code "66") (name "/SPI_MISO") (class "Default")
      (node (ref "SPI") (pin "2") (pinfunction "2_2") (pintype "passive"))
      (node (ref "U4") (pin "79") (pinfunction "P6.5/UCB1SOMI/UCB1SCL/C1.2_79") (pintype "power_in"))
      (node (ref "U5") (pin "SO") (pinfunction "MISO_SO") (pintype "bidirectional"))
    )
    (net (code "67") (name "/SPI_MOSI") (class "Default")
      (node (ref "SPI") (pin "4") (pinfunction "4_4") (pintype "passive"))
      (node (ref "U4") (pin "78") (pinfunction "P6.4/UCB1SIMO/UCB1SDA/C1.3_78") (pintype "power_in"))
      (node (ref "U5") (pin "SI") (pinfunction "MOSI_SI") (pintype "bidirectional"))
    )
    (net (code "68") (name "/SPI_SCK") (class "Default")
      (node (ref "SPI") (pin "3") (pinfunction "3_3") (pintype "passive"))
      (node (ref "U4") (pin "77") (pinfunction "P6.3/UCB1CLK/C1.4_77") (pintype "power_in"))
      (node (ref "U5") (pin "SCK") (pinfunction "SCK_SCK") (pintype "bidirectional"))
    )
    (net (code "69") (name "/TX0") (class "Default")
      (node (ref "PROG") (pin "3") (pinfunction "3_3") (pintype "passive"))
      (node (ref "U4") (pin "7") (pinfunction "P1.3/UCA0TXD/UCA0SIMO_7") (pintype "power_in"))
    )
    (net (code "70") (name "/TX2") (class "Default")
      (node (ref "RX2/TX2") (pin "2") (pinfunction "2_2") (pintype "passive"))
      (node (ref "U4") (pin "35") (pinfunction "P3.3/PM_UCA2TXD/PM_UCA2SIMO_35") (pintype "power_in"))
    )
    (net (code "71") (name "/TX3") (class "Default")
      (node (ref "U13") (pin "P$7") (pinfunction "P$7_P$7") (pintype "bidirectional"))
      (node (ref "U4") (pin "99") (pinfunction "P9.7/UCA3TXD/UCA3SIMO_99") (pintype "power_in"))
    )
    (net (code "72") (name "/VREF_M") (class "Default")
      (node (ref "U10") (pin "1") (pinfunction "REF_1") (pintype "bidirectional"))
      (node (ref "U11") (pin "1") (pinfunction "REF_1") (pintype "bidirectional"))
      (node (ref "U12") (pin "1") (pinfunction "REF_1") (pintype "bidirectional"))
      (node (ref "U8") (pin "2") (pinfunction "OUT_2") (pintype "output"))
      (node (ref "U9") (pin "1") (pinfunction "REF_1") (pintype "bidirectional"))
    )
    (net (code "73") (name "/V_MOTOR") (class "Default")
      (node (ref "C10") (pin "2") (pinfunction "2_2") (pintype "passive"))
      (node (ref "C12") (pin "2") (pinfunction "2_2") (pintype "passive"))
      (node (ref "U2") (pin "1") (pinfunction "VCC_1") (pintype "power_in"))
      (node (ref "U3") (pin "1") (pinfunction "VCC_1") (pintype "power_in"))
      (node (ref "VMOT_SEL") (pin "2") (pinfunction "2_2") (pintype "passive"))
    )
    (net (code "74") (name "/V_MOTOR2") (class "Default")
      (node (ref "C30") (pin "2") (pinfunction "2_2") (pintype "passive"))
      (node (ref "C31") (pin "2") (pinfunction "2_2") (pintype "passive"))
      (node (ref "U6") (pin "1") (pinfunction "VCC_1") (pintype "power_in"))
      (node (ref "U7") (pin "1") (pinfunction "VCC_1") (pintype "power_in"))
      (node (ref "VMOT_SEL2") (pin "2") (pinfunction "2_2") (pintype "passive"))
    )
    (net (code "75") (name "5VEN") (class "Default")
      (node (ref "R4") (pin "1") (pinfunction "1_1") (pintype "passive"))
      (node (ref "U1") (pin "9") (pinfunction "EN_9") (pintype "input"))
      (node (ref "U4") (pin "17") (pinfunction "P2.1/PM_UCA1CLK_17") (pintype "power_in"))
    )
    (net (code "76") (name "AGND") (class "Default")
      (node (ref "ANALOG") (pin "20") (pinfunction "20_20") (pintype "passive"))
      (node (ref "C16") (pin "2") (pinfunction "2_2") (pintype "passive"))
      (node (ref "C26") (pin "2") (pinfunction "2_2") (pintype "passive"))
      (node (ref "C27") (pin "1") (pinfunction "1_1") (pintype "passive"))
      (node (ref "C28") (pin "1") (pinfunction "1_1") (pintype "passive"))
      (node (ref "C29") (pin "1") (pinfunction "1_1") (pintype "passive"))
      (node (ref "C32") (pin "1") (pinfunction "1_1") (pintype "passive"))
      (node (ref "C33") (pin "1") (pinfunction "1_1") (pintype "passive"))
      (node (ref "C34") (pin "1") (pinfunction "1_1") (pintype "passive"))
      (node (ref "C35") (pin "1") (pinfunction "1_1") (pintype "passive"))
      (node (ref "C36") (pin "1") (pinfunction "1_1") (pintype "passive"))
      (node (ref "R14") (pin "2") (pinfunction "2_2") (pintype "passive"))
      (node (ref "U$100") (pin "AGND") (pinfunction "AGND_AGND") (pintype "output"))
      (node (ref "U10") (pin "2") (pinfunction "GND_2") (pintype "bidirectional"))
      (node (ref "U11") (pin "2") (pinfunction "GND_2") (pintype "bidirectional"))
      (node (ref "U12") (pin "2") (pinfunction "GND_2") (pintype "bidirectional"))
      (node (ref "U4") (pin "40") (pinfunction "AVSS3_40") (pintype "power_in"))
      (node (ref "U4") (pin "43") (pinfunction "AVSS1_43") (pintype "power_in"))
      (node (ref "U4") (pin "84") (pinfunction "AVSS2_84") (pintype "power_in"))
      (node (ref "U8") (pin "3") (pinfunction "GND_3") (pintype "power_in"))
      (node (ref "U9") (pin "2") (pinfunction "GND_2") (pintype "bidirectional"))
    )
    (net (code "77") (name "GND") (class "Default")
      (node (ref "C1") (pin "1") (pinfunction "1_1") (pintype "passive"))
      (node (ref "C10") (pin "1") (pinfunction "1_1") (pintype "passive"))
      (node (ref "C11") (pin "1") (pinfunction "1_1") (pintype "passive"))
      (node (ref "C12") (pin "1") (pinfunction "1_1") (pintype "passive"))
      (node (ref "C13") (pin "-") (pinfunction "-_-") (pintype "passive"))
      (node (ref "C14") (pin "1") (pinfunction "1_1") (pintype "passive"))
      (node (ref "C15") (pin "-") (pinfunction "-_-") (pintype "passive"))
      (node (ref "C17") (pin "2") (pinfunction "2_2") (pintype "passive"))
      (node (ref "C18") (pin "1") (pinfunction "1_1") (pintype "passive"))
      (node (ref "C19") (pin "2") (pinfunction "2_2") (pintype "passive"))
      (node (ref "C2") (pin "2") (pinfunction "2_2") (pintype "passive"))
      (node (ref "C20") (pin "1") (pinfunction "1_1") (pintype "passive"))
      (node (ref "C21") (pin "2") (pinfunction "2_2") (pintype "passive"))
      (node (ref "C22") (pin "2") (pinfunction "2_2") (pintype "passive"))
      (node (ref "C23") (pin "1") (pinfunction "1_1") (pintype "passive"))
      (node (ref "C24") (pin "2") (pinfunction "2_2") (pintype "passive"))
      (node (ref "C25") (pin "1") (pinfunction "1_1") (pintype "passive"))
      (node (ref "C30") (pin "1") (pinfunction "1_1") (pintype "passive"))
      (node (ref "C31") (pin "1") (pinfunction "1_1") (pintype "passive"))
      (node (ref "C4") (pin "2") (pinfunction "2_2") (pintype "passive"))
      (node (ref "C5") (pin "2") (pinfunction "2_2") (pintype "passive"))
      (node (ref "C6") (pin "2") (pinfunction "2_2") (pintype "passive"))
      (node (ref "C7") (pin "2") (pinfunction "2_2") (pintype "passive"))
      (node (ref "C9") (pin "2") (pinfunction "2_2") (pintype "passive"))
      (node (ref "DIGITAL_IO") (pin "2") (pinfunction "2_2") (pintype "passive"))
      (node (ref "DIGITAL_IO") (pin "22") (pinfunction "22_22") (pintype "passive"))
      (node (ref "IC1") (pin "1") (pinfunction "GND_1") (pintype "power_in"))
      (node (ref "IC1") (pin "5") (pinfunction "SDO_5") (pintype "input"))
      (node (ref "IC1") (pin "7") (pinfunction "GND_7") (pintype "power_in"))
      (node (ref "IC2") (pin "10") (pinfunction "PIN10_10") (pintype "bidirectional"))
      (node (ref "IC2") (pin "15") (pinfunction "PIN15_15") (pintype "bidirectional"))
      (node (ref "IC2") (pin "16") (pinfunction "PIN16_16") (pintype "bidirectional"))
      (node (ref "IC2") (pin "17") (pinfunction "COM3_17") (pintype "bidirectional"))
      (node (ref "IC2") (pin "18") (pinfunction "COM2_18") (pintype "bidirectional"))
      (node (ref "IC2") (pin "2") (pinfunction "GND_2") (pintype "bidirectional"))
      (node (ref "IC2") (pin "25") (pinfunction "GNDIO_25") (pintype "bidirectional"))
      (node (ref "IC2") (pin "5") (pinfunction "PS1_5") (pintype "bidirectional"))
      (node (ref "IC2") (pin "6") (pinfunction "PS0_6") (pintype "bidirectional"))
      (node (ref "J1") (pin "5") (pinfunction "5_5") (pintype "bidirectional"))
      (node (ref "JP2") (pin "11") (pinfunction "11_11") (pintype "passive"))
      (node (ref "JP2") (pin "12") (pinfunction "12_12") (pintype "passive"))
      (node (ref "JP2") (pin "5") (pinfunction "5_5") (pintype "passive"))
      (node (ref "JP2") (pin "6") (pinfunction "6_6") (pintype "passive"))
      (node (ref "JP2") (pin "7") (pinfunction "7_7") (pintype "passive"))
      (node (ref "JP2") (pin "8") (pinfunction "8_8") (pintype "passive"))
      (node (ref "LED33_J") (pin "1") (pinfunction "1_1") (pintype "passive"))
      (node (ref "LED5_J") (pin "1") (pinfunction "1_1") (pintype "passive"))
      (node (ref "PROG") (pin "1") (pinfunction "1_1") (pintype "passive"))
      (node (ref "Q2") (pin "P3") (pinfunction "GND_P3") (pintype "power_in"))
      (node (ref "R6") (pin "1") (pinfunction "1_1") (pintype "passive"))
      (node (ref "R7") (pin "1") (pinfunction "1_1") (pintype "passive"))
      (node (ref "RX1/TX1") (pin "1") (pinfunction "1_1") (pintype "passive"))
      (node (ref "RX2/TX2") (pin "1") (pinfunction "1_1") (pintype "passive"))
      (node (ref "U$100") (pin "DGND") (pinfunction "DGND_DGND") (pintype "output"))
      (node (ref "U$100") (pin "GND") (pinfunction "GND_GND") (pintype "power_in"))
      (node (ref "U1") (pin "EXPAD") (pinfunction "GND_EXPAD") (pintype "power_in"))
      (node (ref "U1") (pin "GND1") (pinfunction "GND1_GND1") (pintype "power_in"))
      (node (ref "U1") (pin "GND2") (pinfunction "GND2_GND2") (pintype "power_in"))
      (node (ref "U1") (pin "GND3") (pinfunction "GND3_GND3") (pintype "power_in"))
      (node (ref "U1") (pin "GND4") (pinfunction "GND4_GND4") (pintype "power_in"))
      (node (ref "U1") (pin "GND5") (pinfunction "GND5_GND5") (pintype "power_in"))
      (node (ref "U13") (pin "P$1") (pinfunction "P$1_P$1") (pintype "bidirectional"))
      (node (ref "U13") (pin "P$11") (pinfunction "P$11_P$11") (pintype "bidirectional"))
      (node (ref "U13") (pin "P$20") (pinfunction "P$20_P$20") (pintype "bidirectional"))
      (node (ref "U13") (pin "P$21") (pinfunction "P$21_P$21") (pintype "bidirectional"))
      (node (ref "U13") (pin "P$22") (pinfunction "P$22_P$22") (pintype "bidirectional"))
      (node (ref "U13") (pin "P$24") (pinfunction "P$24_P$24") (pintype "bidirectional"))
      (node (ref "U13") (pin "P$26") (pinfunction "P$26_P$26") (pintype "bidirectional"))
      (node (ref "U13") (pin "P$27") (pinfunction "P$27_P$27") (pintype "bidirectional"))
      (node (ref "U13") (pin "P$28") (pinfunction "P$28_P$28") (pintype "bidirectional"))
      (node (ref "U13") (pin "P$33") (pinfunction "P$33_P$33") (pintype "bidirectional"))
      (node (ref "U13") (pin "P$41") (pinfunction "P$41_P$41") (pintype "bidirectional"))
      (node (ref "U13") (pin "P$47") (pinfunction "P$47_P$47") (pintype "bidirectional"))
      (node (ref "U13") (pin "P$8") (pinfunction "P$8_P$8") (pintype "bidirectional"))
      (node (ref "U2") (pin "13") (pinfunction "EPAD_13") (pintype "passive"))
      (node (ref "U2") (pin "6") (pinfunction "GND_6") (pintype "passive"))
      (node (ref "U3") (pin "13") (pinfunction "EPAD_13") (pintype "passive"))
      (node (ref "U3") (pin "6") (pinfunction "GND_6") (pintype "passive"))
      (node (ref "U4") (pin "15") (pinfunction "DVSS1_15") (pintype "power_in"))
      (node (ref "U4") (pin "72") (pinfunction "DVSS2_72") (pintype "power_in"))
      (node (ref "U4") (pin "82") (pinfunction "DVSS3_82") (pintype "power_in"))
      (node (ref "U5") (pin "VSS") (pinfunction "GND_VSS") (pintype "bidirectional"))
      (node (ref "U6") (pin "13") (pinfunction "EPAD_13") (pintype "passive"))
      (node (ref "U6") (pin "6") (pinfunction "GND_6") (pintype "passive"))
      (node (ref "U7") (pin "13") (pinfunction "EPAD_13") (pintype "passive"))
      (node (ref "U7") (pin "6") (pinfunction "GND_6") (pintype "passive"))
    )
    (net (code "78") (name "LED0") (class "Default")
      (node (ref "LED0") (pin "A") (pinfunction "A_A") (pintype "passive"))
      (node (ref "U4") (pin "100") (pinfunction "P10.0/UCB3STE_100") (pintype "power_in"))
    )
    (net (code "79") (name "LED1") (class "Default")
      (node (ref "LED1") (pin "A") (pinfunction "A_A") (pintype "passive"))
      (node (ref "U4") (pin "1") (pinfunction "P10.1/UCB3CLK_1") (pintype "power_in"))
    )
    (net (code "80") (name "M1IN1") (class "Default")
      (node (ref "U2") (pin "10") (pinfunction "AIN1_/_APHASE_10") (pintype "input"))
      (node (ref "U4") (pin "38") (pinfunction "P3.6/PM_UCB2SIMO/PM_UCB2SDA_38") (pintype "power_in"))
    )
    (net (code "81") (name "M1IN2") (class "Default")
      (node (ref "U2") (pin "9") (pinfunction "AIN2_/_AENBL_9") (pintype "input"))
      (node (ref "U4") (pin "20") (pinfunction "P2.4/PM_TA0.1_20") (pintype "power_in"))
    )
    (net (code "82") (name "M2IN1") (class "Default")
      (node (ref "U2") (pin "8") (pinfunction "BIN1_/_BPHASE_8") (pintype "input"))
      (node (ref "U4") (pin "21") (pinfunction "P2.5/PM_TA0.2_21") (pintype "power_in"))
    )
    (net (code "83") (name "M2IN2") (class "Default")
      (node (ref "U2") (pin "7") (pinfunction "BIN2_/_BENBL_7") (pintype "input"))
      (node (ref "U4") (pin "22") (pinfunction "P2.6/PM_TA0.3_22") (pintype "power_in"))
    )
    (net (code "84") (name "M3IN1") (class "Default")
      (node (ref "U3") (pin "10") (pinfunction "AIN1_/_APHASE_10") (pintype "input"))
      (node (ref "U4") (pin "23") (pinfunction "P2.7/PM_TA0.4_23") (pintype "power_in"))
    )
    (net (code "85") (name "M3IN2") (class "Default")
      (node (ref "U3") (pin "9") (pinfunction "AIN2_/_AENBL_9") (pintype "input"))
      (node (ref "U4") (pin "24") (pinfunction "P10.4/TA3.0/C0.7_24") (pintype "power_in"))
    )
    (net (code "86") (name "M4IN1") (class "Default")
      (node (ref "U3") (pin "8") (pinfunction "BIN1_/_BPHASE_8") (pintype "input"))
      (node (ref "U4") (pin "25") (pinfunction "P10.5/TA3.1/C0.6_25") (pintype "power_in"))
    )
    (net (code "87") (name "M4IN2") (class "Default")
      (node (ref "U3") (pin "7") (pinfunction "BIN2_/_BENBL_7") (pintype "input"))
      (node (ref "U4") (pin "26") (pinfunction "P7.4/PM_TA1.4/C0.5_26") (pintype "power_in"))
    )
    (net (code "88") (name "M5IN1") (class "Default")
      (node (ref "U4") (pin "27") (pinfunction "P7.5/PM_TA1.3/C0.4_27") (pintype "power_in"))
      (node (ref "U7") (pin "10") (pinfunction "AIN1_/_APHASE_10") (pintype "input"))
    )
    (net (code "89") (name "M5IN2") (class "Default")
      (node (ref "U4") (pin "28") (pinfunction "P7.6/PM_TA1.2/C0.3_28") (pintype "power_in"))
      (node (ref "U7") (pin "9") (pinfunction "AIN2_/_AENBL_9") (pintype "input"))
    )
    (net (code "90") (name "M6IN1") (class "Default")
      (node (ref "U4") (pin "30") (pinfunction "P8.0/UCB3STE/TA1.0/C0.1_30") (pintype "power_in"))
      (node (ref "U7") (pin "8") (pinfunction "BIN1_/_BPHASE_8") (pintype "input"))
    )
    (net (code "91") (name "M6IN2") (class "Default")
      (node (ref "U4") (pin "29") (pinfunction "P7.7/PM_TA1.1/C0.2_29") (pintype "power_in"))
      (node (ref "U7") (pin "7") (pinfunction "BIN2_/_BENBL_7") (pintype "input"))
    )
    (net (code "92") (name "M7IN1") (class "Default")
      (node (ref "U4") (pin "31") (pinfunction "P8.1/UCB3CLK/TA2.0/C0.0_31") (pintype "power_in"))
      (node (ref "U6") (pin "10") (pinfunction "AIN1_/_APHASE_10") (pintype "input"))
    )
    (net (code "93") (name "M7IN2") (class "Default")
      (node (ref "U4") (pin "32") (pinfunction "P3.0/PM_UCA2STE_32") (pintype "power_in"))
      (node (ref "U6") (pin "9") (pinfunction "AIN2_/_AENBL_9") (pintype "input"))
    )
    (net (code "94") (name "M8IN1") (class "Default")
      (node (ref "U4") (pin "33") (pinfunction "P3.1/PM_UCA2CLK_33") (pintype "power_in"))
      (node (ref "U6") (pin "8") (pinfunction "BIN1_/_BPHASE_8") (pintype "input"))
    )
    (net (code "95") (name "M8IN2") (class "Default")
      (node (ref "U4") (pin "36") (pinfunction "P3.4/PM_UCB2STE_36") (pintype "power_in"))
      (node (ref "U6") (pin "7") (pinfunction "BIN2_/_BENBL_7") (pintype "input"))
    )
    (net (code "96") (name "M1234SLEEP") (class "Default")
      (node (ref "U2") (pin "11") (pinfunction "MODE_11") (pintype "input"))
      (node (ref "U2") (pin "12") (pinfunction "NSLEEP_12") (pintype "input"))
      (node (ref "U3") (pin "11") (pinfunction "MODE_11") (pintype "input"))
      (node (ref "U3") (pin "12") (pinfunction "NSLEEP_12") (pintype "input"))
      (node (ref "U4") (pin "16") (pinfunction "P2.0/PM_UCA1STE_16") (pintype "power_in"))
    )
    (net (code "97") (name "M5678SLEEP") (class "Default")
      (node (ref "U4") (pin "37") (pinfunction "P3.5/PM_UCB2CLK_37") (pintype "power_in"))
      (node (ref "U6") (pin "11") (pinfunction "MODE_11") (pintype "input"))
      (node (ref "U6") (pin "12") (pinfunction "NSLEEP_12") (pintype "input"))
      (node (ref "U7") (pin "11") (pinfunction "MODE_11") (pintype "input"))
      (node (ref "U7") (pin "12") (pinfunction "NSLEEP_12") (pintype "input"))
    )
    (net (code "98") (name "Net-(3V-PadC)") (class "Default")
      (node (ref "3V") (pin "C") (pinfunction "C_C") (pintype "passive"))
      (node (ref "R9") (pin "2") (pinfunction "2_2") (pintype "passive"))
    )
    (net (code "99") (name "Net-(5V-PadC)") (class "Default")
      (node (ref "5V") (pin "C") (pinfunction "C_C") (pintype "passive"))
      (node (ref "R2") (pin "2") (pinfunction "2_2") (pintype "passive"))
    )
    (net (code "100") (name "Net-(433MHZ-Pad1)") (class "Default")
      (node (ref "433MHZ") (pin "1") (pinfunction "1_1") (pintype "passive"))
      (node (ref "U13") (pin "P$25") (pinfunction "P$25_P$25") (pintype "bidirectional"))
    )
    (net (code "101") (name "Net-(868MHZ-Pad1)") (class "Default")
      (node (ref "868MHZ") (pin "1") (pinfunction "1_1") (pintype "passive"))
      (node (ref "U13") (pin "P$23") (pinfunction "P$23_P$23") (pintype "bidirectional"))
    )
    (net (code "102") (name "Net-(IC2-CAP)") (class "Default")
      (node (ref "C18") (pin "2") (pinfunction "2_2") (pintype "passive"))
      (node (ref "IC2") (pin "9") (pinfunction "CAP_9") (pintype "bidirectional"))
    )
    (net (code "103") (name "Net-(IC2-XIN32)") (class "Default")
      (node (ref "C19") (pin "1") (pinfunction "1_1") (pintype "passive"))
      (node (ref "IC2") (pin "27") (pinfunction "XIN32_27") (pintype "bidirectional"))
      (node (ref "Q1") (pin "2") (pinfunction "2_2") (pintype "passive"))
    )
    (net (code "104") (name "Net-(IC2-XOUT32)") (class "Default")
      (node (ref "C17") (pin "1") (pinfunction "1_1") (pintype "passive"))
      (node (ref "IC2") (pin "26") (pinfunction "XOUT32_26") (pintype "bidirectional"))
      (node (ref "Q1") (pin "1") (pinfunction "1_1") (pintype "passive"))
    )
    (net (code "105") (name "Net-(L1-2)") (class "Default")
      (node (ref "L1") (pin "P$2") (pinfunction "2_P$2") (pintype "passive"))
      (node (ref "U1") (pin "1") (pinfunction "SW_1") (pintype "power_in"))
      (node (ref "U1") (pin "2") (pinfunction "SW_2") (pintype "power_in"))
    )
    (net (code "106") (name "Net-(LED0-PadC)") (class "Default")
      (node (ref "LED0") (pin "C") (pinfunction "C_C") (pintype "passive"))
      (node (ref "R7") (pin "2") (pinfunction "2_2") (pintype "passive"))
    )
    (net (code "107") (name "Net-(LED1-PadC)") (class "Default")
      (node (ref "LED1") (pin "C") (pinfunction "C_C") (pintype "passive"))
      (node (ref "R6") (pin "2") (pinfunction "2_2") (pintype "passive"))
    )
    (net (code "108") (name "Net-(LED5_J-Pad2)") (class "Default")
      (node (ref "LED5_J") (pin "2") (pinfunction "2_2") (pintype "passive"))
      (node (ref "R2") (pin "1") (pinfunction "1_1") (pintype "passive"))
    )
    (net (code "109") (name "Net-(LED33_J-Pad2)") (class "Default")
      (node (ref "LED33_J") (pin "2") (pinfunction "2_2") (pintype "passive"))
      (node (ref "R9") (pin "1") (pinfunction "1_1") (pintype "passive"))
    )
    (net (code "110") (name "Net-(M5/M1-Pad1)") (class "Default")
      (node (ref "M5/M1") (pin "1") (pinfunction "1_1") (pintype "passive"))
      (node (ref "RS4") (pin "I2") (pinfunction "I2_I2") (pintype "bidirectional"))
    )
    (net (code "111") (name "Net-(M5/M1-Pad3)") (class "Default")
      (node (ref "M5/M1") (pin "3") (pinfunction "3_3") (pintype "passive"))
      (node (ref "RS3") (pin "I2") (pinfunction "I2_I2") (pintype "bidirectional"))
    )
    (net (code "112") (name "Net-(M7/M1-Pad1)") (class "Default")
      (node (ref "M7/M1") (pin "1") (pinfunction "1_1") (pintype "passive"))
      (node (ref "RS2") (pin "I2") (pinfunction "I2_I2") (pintype "bidirectional"))
    )
    (net (code "113") (name "Net-(M7/M1-Pad3)") (class "Default")
      (node (ref "M7/M1") (pin "3") (pinfunction "3_3") (pintype "passive"))
      (node (ref "RS1") (pin "I2") (pinfunction "I2_I2") (pintype "bidirectional"))
    )
    (net (code "114") (name "Net-(Q2-1)") (class "Default")
      (node (ref "C25") (pin "2") (pinfunction "2_2") (pintype "passive"))
      (node (ref "Q2") (pin "P1") (pinfunction "1_P1") (pintype "bidirectional"))
      (node (ref "U4") (pin "42") (pinfunction "PJ.1/LFXOUT_42") (pintype "power_in"))
    )
    (net (code "115") (name "Net-(Q2-2)") (class "Default")
      (node (ref "C23") (pin "2") (pinfunction "2_2") (pintype "passive"))
      (node (ref "Q2") (pin "P2") (pinfunction "2_P2") (pintype "bidirectional"))
      (node (ref "U4") (pin "41") (pinfunction "PJ.0/LFXIN_41") (pintype "power_in"))
    )
    (net (code "116") (name "Net-(U1-PG)") (class "Default")
      (node (ref "R5") (pin "1") (pinfunction "1_1") (pintype "passive"))
      (node (ref "U1") (pin "5") (pinfunction "PG_5") (pintype "output"))
    )
    (net (code "117") (name "Net-(U1-SS)") (class "Default")
      (node (ref "C5") (pin "1") (pinfunction "1_1") (pintype "passive"))
      (node (ref "U1") (pin "6") (pinfunction "SS_6") (pintype "bidirectional"))
    )
    (net (code "118") (name "Net-(U2-AOUT1)") (class "Default")
      (node (ref "M1/M2") (pin "1") (pinfunction "1_1") (pintype "passive"))
      (node (ref "U2") (pin "2") (pinfunction "AOUT1_2") (pintype "output"))
    )
    (net (code "119") (name "Net-(U2-AOUT2)") (class "Default")
      (node (ref "M1/M2") (pin "2") (pinfunction "2_2") (pintype "passive"))
      (node (ref "U2") (pin "3") (pinfunction "AOUT2_3") (pintype "output"))
    )
    (net (code "120") (name "Net-(U2-BOUT1)") (class "Default")
      (node (ref "M1/M2") (pin "3") (pinfunction "3_3") (pintype "passive"))
      (node (ref "U2") (pin "4") (pinfunction "BOUT1_4") (pintype "output"))
    )
    (net (code "121") (name "Net-(U2-BOUT2)") (class "Default")
      (node (ref "M1/M2") (pin "4") (pinfunction "4_4") (pintype "passive"))
      (node (ref "U2") (pin "5") (pinfunction "BOUT2_5") (pintype "output"))
    )
    (net (code "122") (name "Net-(U3-AOUT1)") (class "Default")
      (node (ref "M3/M4") (pin "1") (pinfunction "1_1") (pintype "passive"))
      (node (ref "U3") (pin "2") (pinfunction "AOUT1_2") (pintype "output"))
    )
    (net (code "123") (name "Net-(U3-AOUT2)") (class "Default")
      (node (ref "M3/M4") (pin "2") (pinfunction "2_2") (pintype "passive"))
      (node (ref "U3") (pin "3") (pinfunction "AOUT2_3") (pintype "output"))
    )
    (net (code "124") (name "Net-(U3-BOUT1)") (class "Default")
      (node (ref "M3/M4") (pin "3") (pinfunction "3_3") (pintype "passive"))
      (node (ref "U3") (pin "4") (pinfunction "BOUT1_4") (pintype "output"))
    )
    (net (code "125") (name "Net-(U3-BOUT2)") (class "Default")
      (node (ref "M3/M4") (pin "4") (pinfunction "4_4") (pintype "passive"))
      (node (ref "U3") (pin "5") (pinfunction "BOUT2_5") (pintype "output"))
    )
    (net (code "126") (name "Net-(U4-DCOR)") (class "Default")
      (node (ref "R14") (pin "1") (pinfunction "1_1") (pintype "passive"))
      (node (ref "U4") (pin "44") (pinfunction "DCOR_44") (pintype "power_in"))
    )
    (net (code "127") (name "Net-(U4-SWCLKTCK)") (class "Default")
      (node (ref "PROG") (pin "5") (pinfunction "5_5") (pintype "passive"))
      (node (ref "U4") (pin "95") (pinfunction "SWCLKTCK_95") (pintype "power_in"))
    )
    (net (code "128") (name "Net-(U4-SWDIOTMS)") (class "Default")
      (node (ref "PROG") (pin "6") (pinfunction "6_6") (pintype "passive"))
      (node (ref "U4") (pin "94") (pinfunction "SWDIOTMS_94") (pintype "power_in"))
    )
    (net (code "129") (name "Net-(U4-VCORE)") (class "Default")
      (node (ref "C14") (pin "2") (pinfunction "2_2") (pintype "passive"))
      (node (ref "C15") (pin "+") (pinfunction "+_+") (pintype "passive"))
      (node (ref "L2") (pin "1") (pinfunction "1_1") (pintype "passive"))
      (node (ref "U4") (pin "12") (pinfunction "VCORE_12") (pintype "power_in"))
    )
    (net (code "130") (name "Net-(U4-VSW)") (class "Default")
      (node (ref "L2") (pin "2") (pinfunction "2_2") (pintype "passive"))
      (node (ref "U4") (pin "14") (pinfunction "VSW_14") (pintype "power_in"))
    )
    (net (code "131") (name "Net-(U6-AOUT1)") (class "Default")
      (node (ref "RS2") (pin "I1") (pinfunction "I1_I1") (pintype "bidirectional"))
      (node (ref "U6") (pin "2") (pinfunction "AOUT1_2") (pintype "output"))
    )
    (net (code "132") (name "Net-(U6-AOUT2)") (class "Default")
      (node (ref "M7/M1") (pin "2") (pinfunction "2_2") (pintype "passive"))
      (node (ref "U6") (pin "3") (pinfunction "AOUT2_3") (pintype "output"))
    )
    (net (code "133") (name "Net-(U6-BOUT1)") (class "Default")
      (node (ref "RS1") (pin "I1") (pinfunction "I1_I1") (pintype "bidirectional"))
      (node (ref "U6") (pin "4") (pinfunction "BOUT1_4") (pintype "output"))
    )
    (net (code "134") (name "Net-(U6-BOUT2)") (class "Default")
      (node (ref "M7/M1") (pin "4") (pinfunction "4_4") (pintype "passive"))
      (node (ref "U6") (pin "5") (pinfunction "BOUT2_5") (pintype "output"))
    )
    (net (code "135") (name "Net-(U7-AOUT2)") (class "Default")
      (node (ref "M5/M1") (pin "2") (pinfunction "2_2") (pintype "passive"))
      (node (ref "U7") (pin "3") (pinfunction "AOUT2_3") (pintype "output"))
    )
    (net (code "136") (name "Net-(U7-BOUT1)") (class "Default")
      (node (ref "RS3") (pin "I1") (pinfunction "I1_I1") (pintype "bidirectional"))
      (node (ref "U7") (pin "4") (pinfunction "BOUT1_4") (pintype "output"))
    )
    (net (code "137") (name "Net-(U7-BOUT2)") (class "Default")
      (node (ref "M5/M1") (pin "4") (pinfunction "4_4") (pintype "passive"))
      (node (ref "U7") (pin "5") (pinfunction "BOUT2_5") (pintype "output"))
    )
    (net (code "138") (name "Net-(U9-IN+)") (class "Default")
      (node (ref "RS1") (pin "V1") (pinfunction "V1_V1") (pintype "bidirectional"))
      (node (ref "U9") (pin "4") (pinfunction "IN+_4") (pintype "bidirectional"))
    )
    (net (code "139") (name "Net-(U9-IN-)") (class "Default")
      (node (ref "RS1") (pin "V2") (pinfunction "V2_V2") (pintype "bidirectional"))
      (node (ref "U9") (pin "5") (pinfunction "IN-_5") (pintype "bidirectional"))
    )
    (net (code "140") (name "Net-(U10-IN+)") (class "Default")
      (node (ref "RS2") (pin "V1") (pinfunction "V1_V1") (pintype "bidirectional"))
      (node (ref "U10") (pin "4") (pinfunction "IN+_4") (pintype "bidirectional"))
    )
    (net (code "141") (name "Net-(U10-IN-)") (class "Default")
      (node (ref "RS2") (pin "V2") (pinfunction "V2_V2") (pintype "bidirectional"))
      (node (ref "U10") (pin "5") (pinfunction "IN-_5") (pintype "bidirectional"))
    )
    (net (code "142") (name "Net-(U11-IN+)") (class "Default")
      (node (ref "RS3") (pin "V1") (pinfunction "V1_V1") (pintype "bidirectional"))
      (node (ref "U11") (pin "4") (pinfunction "IN+_4") (pintype "bidirectional"))
    )
    (net (code "143") (name "Net-(U11-IN-)") (class "Default")
      (node (ref "RS3") (pin "V2") (pinfunction "V2_V2") (pintype "bidirectional"))
      (node (ref "U11") (pin "5") (pinfunction "IN-_5") (pintype "bidirectional"))
    )
    (net (code "144") (name "Net-(U12-IN+)") (class "Default")
      (node (ref "RS4") (pin "V1") (pinfunction "V1_V1") (pintype "bidirectional"))
      (node (ref "U12") (pin "4") (pinfunction "IN+_4") (pintype "bidirectional"))
    )
    (net (code "145") (name "Net-(U12-IN-)") (class "Default")
      (node (ref "RS4") (pin "V2") (pinfunction "V2_V2") (pintype "bidirectional"))
      (node (ref "U12") (pin "5") (pinfunction "IN-_5") (pintype "bidirectional"))
    )
    (net (code "146") (name "RX1") (class "Default")
      (node (ref "RX1/TX1") (pin "3") (pinfunction "3_3") (pintype "passive"))
      (node (ref "U4") (pin "18") (pinfunction "P2.2/PM_UCA1RXD/PM_UCA1SOMI_18") (pintype "power_in"))
    )
    (net (code "147") (name "TX1") (class "Default")
      (node (ref "RX1/TX1") (pin "2") (pinfunction "2_2") (pintype "passive"))
      (node (ref "U4") (pin "19") (pinfunction "P2.3/PM_UCA1TXD/PM_UCA1SIMO_19") (pintype "power_in"))
    )
    (net (code "148") (name "unconnected-(IC2-PIN1-Pad1)") (class "Default")
      (node (ref "IC2") (pin "1") (pinfunction "PIN1_1") (pintype "bidirectional"))
    )
    (net (code "149") (name "unconnected-(IC2-PIN7-Pad7)") (class "Default")
      (node (ref "IC2") (pin "7") (pinfunction "PIN7_7") (pintype "bidirectional"))
    )
    (net (code "150") (name "unconnected-(IC2-PIN8-Pad8)") (class "Default")
      (node (ref "IC2") (pin "8") (pinfunction "PIN8_8") (pintype "bidirectional"))
    )
    (net (code "151") (name "unconnected-(IC2-PIN12-Pad12)") (class "Default")
      (node (ref "IC2") (pin "12") (pinfunction "PIN12_12") (pintype "bidirectional"))
    )
    (net (code "152") (name "unconnected-(IC2-PIN13-Pad13)") (class "Default")
      (node (ref "IC2") (pin "13") (pinfunction "PIN13_13") (pintype "bidirectional"))
    )
    (net (code "153") (name "unconnected-(IC2-PIN21-Pad21)") (class "Default")
      (node (ref "IC2") (pin "21") (pinfunction "PIN21_21") (pintype "bidirectional"))
    )
    (net (code "154") (name "unconnected-(IC2-PIN22-Pad22)") (class "Default")
      (node (ref "IC2") (pin "22") (pinfunction "PIN22_22") (pintype "bidirectional"))
    )
    (net (code "155") (name "unconnected-(IC2-PIN23-Pad23)") (class "Default")
      (node (ref "IC2") (pin "23") (pinfunction "PIN23_23") (pintype "bidirectional"))
    )
    (net (code "156") (name "unconnected-(IC2-PIN24-Pad24)") (class "Default")
      (node (ref "IC2") (pin "24") (pinfunction "PIN24_24") (pintype "bidirectional"))
    )
    (net (code "157") (name "unconnected-(U1-HYS-Pad8)") (class "Default")
      (node (ref "U1") (pin "8") (pinfunction "HYS_8") (pintype "output"))
    )
  )
)
